# board2-0.net
KiCad netlist of a schematic drawn in EAGLE
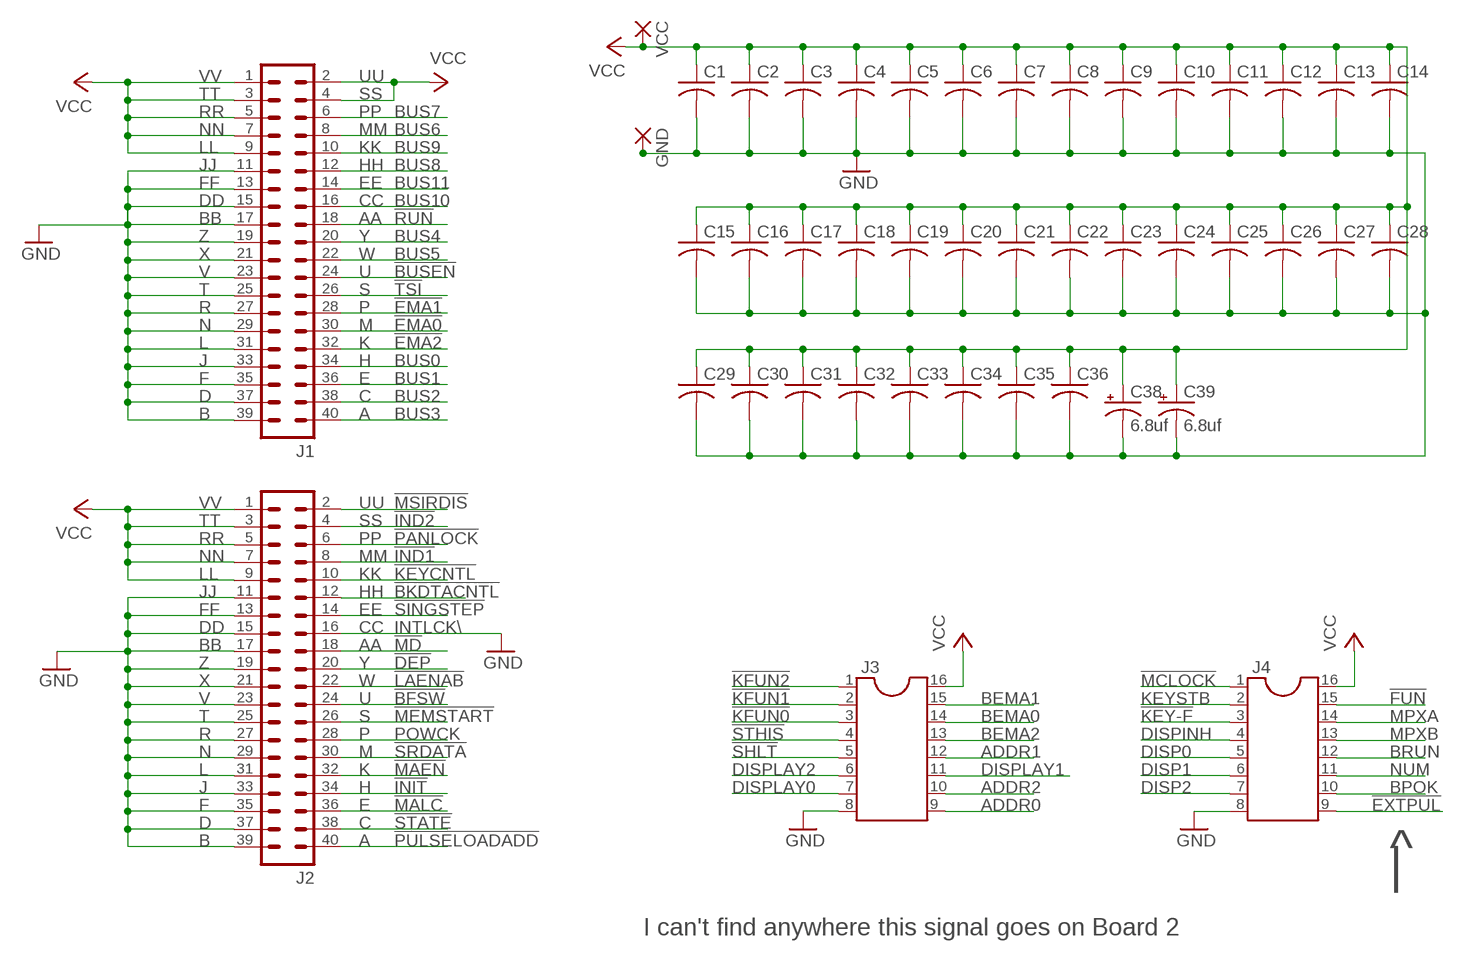
[diagram p0: schematic, sheet 1]
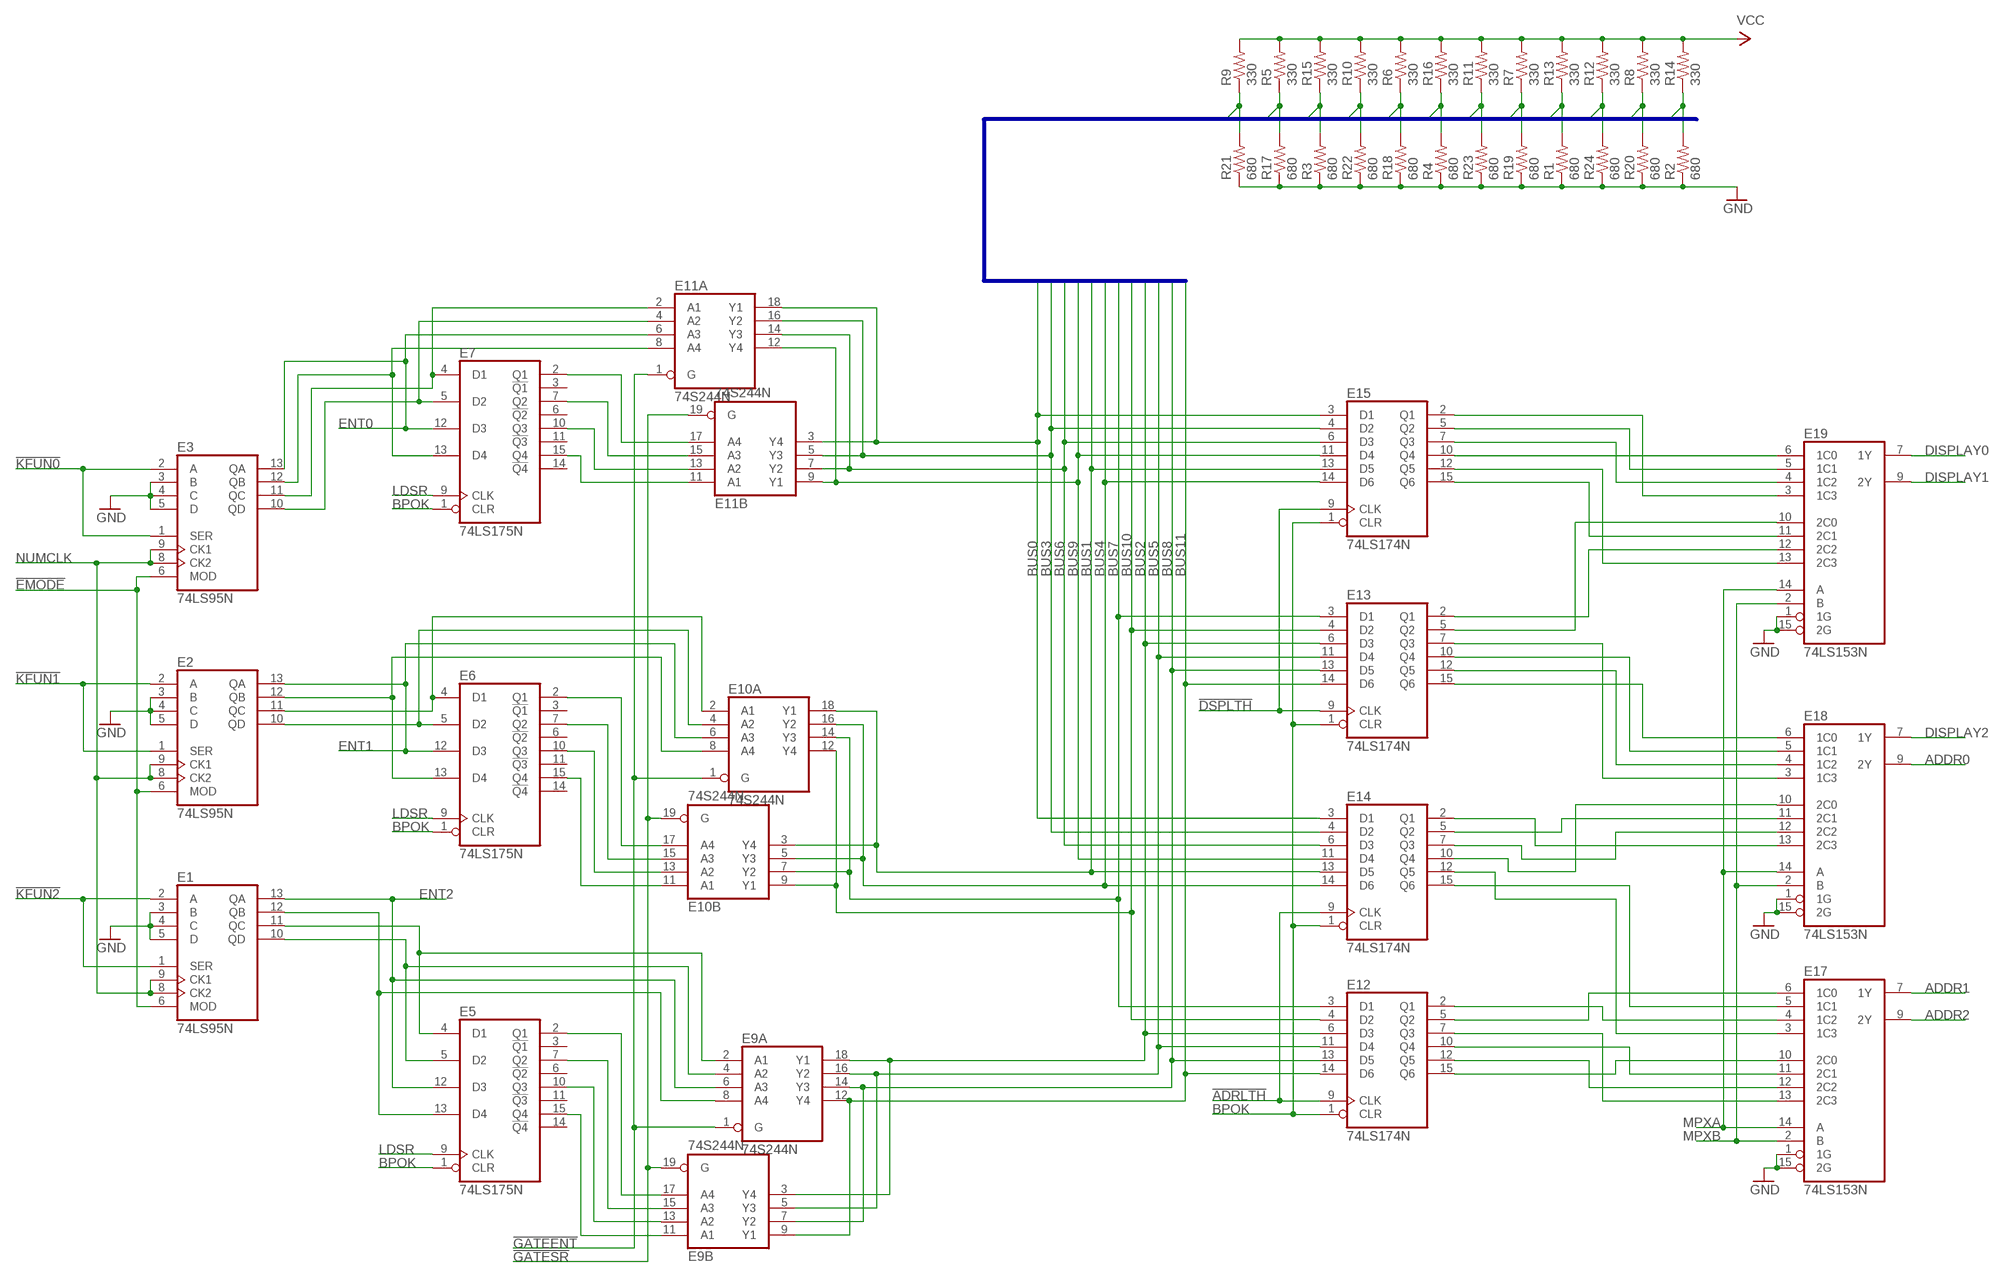
[diagram p1: schematic, sheet 2]
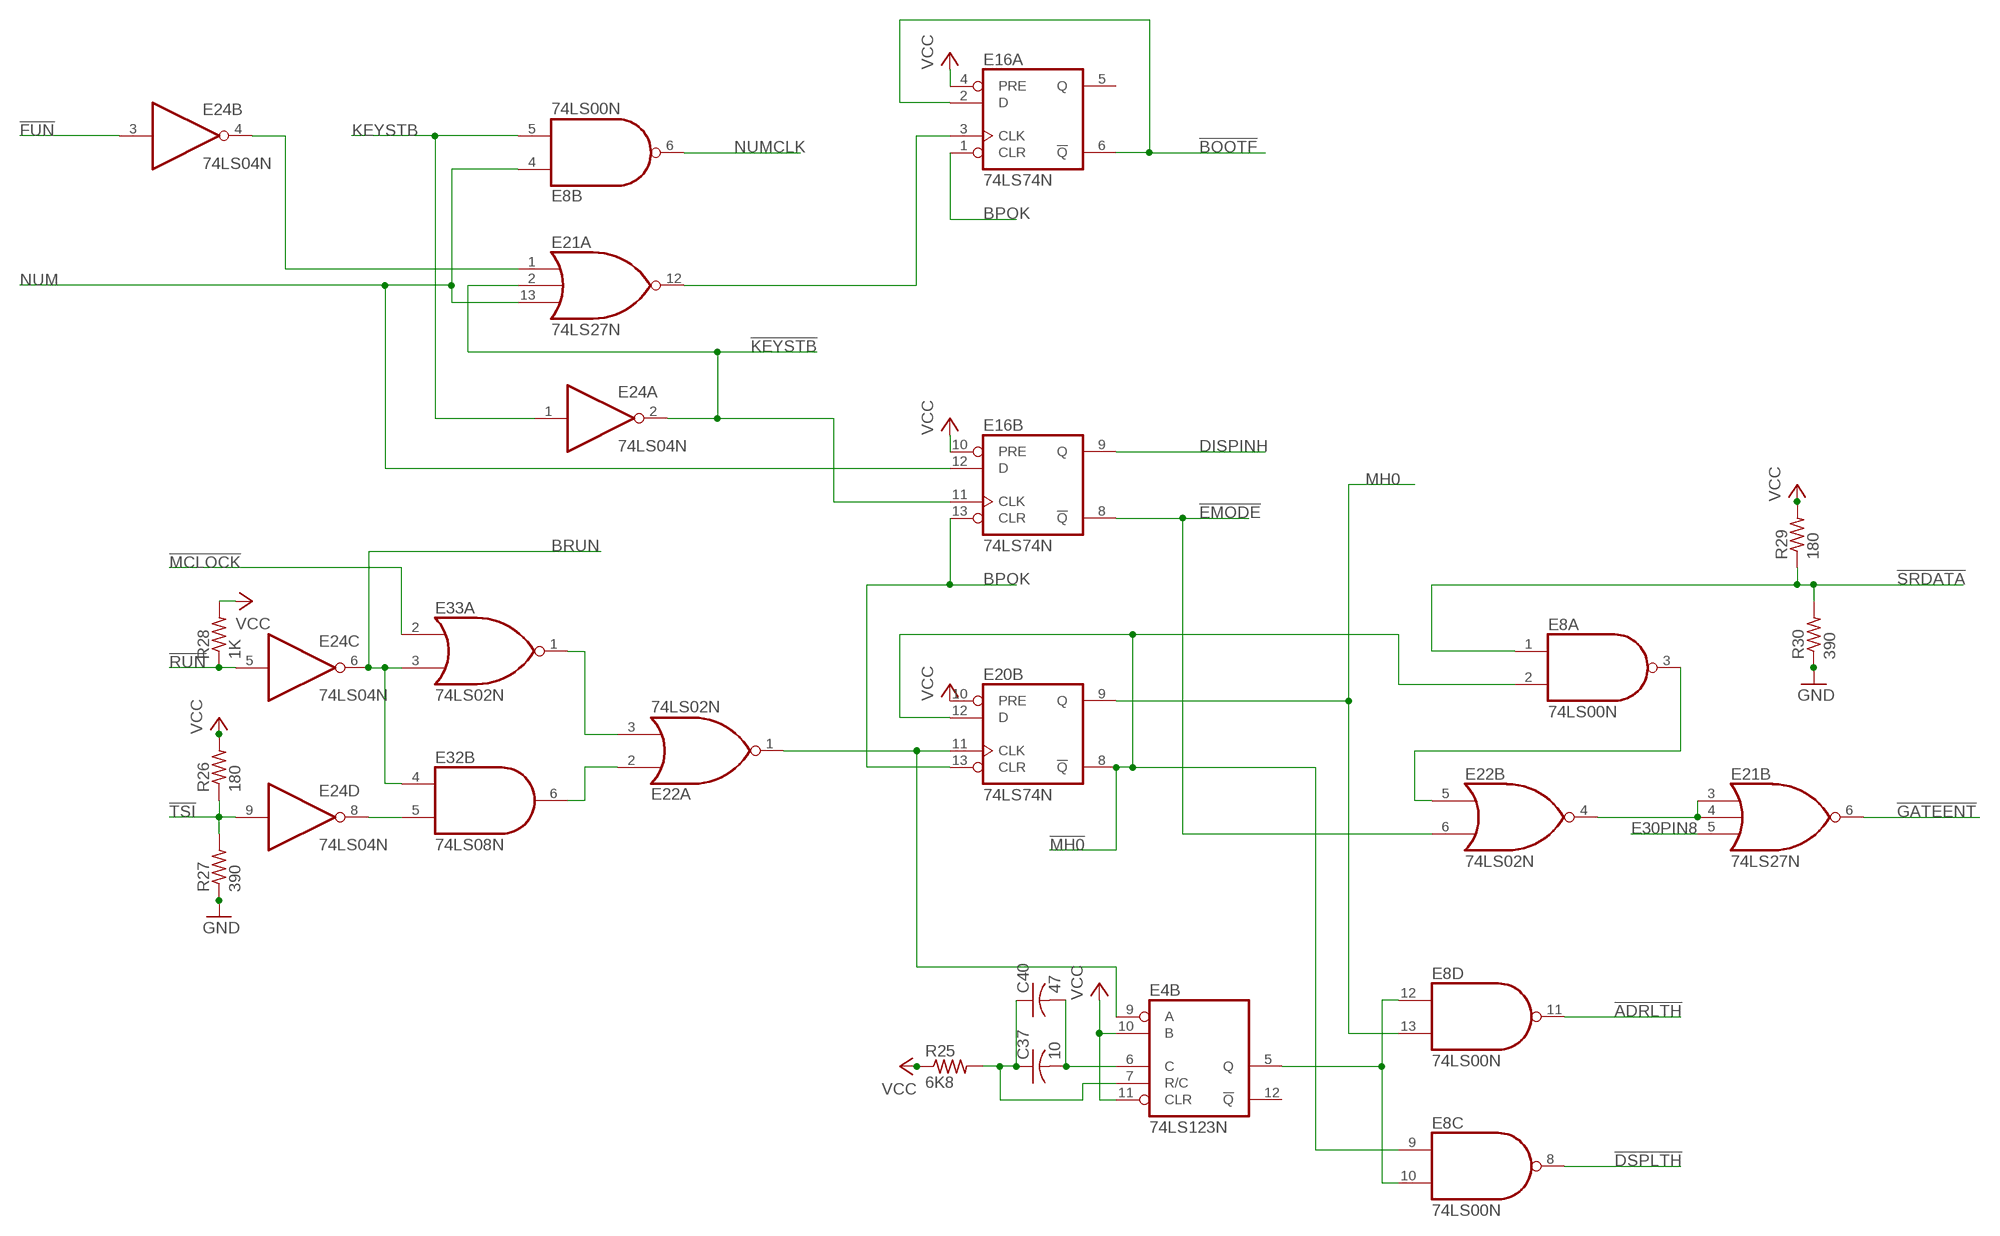
[diagram p2: schematic, sheet 3]
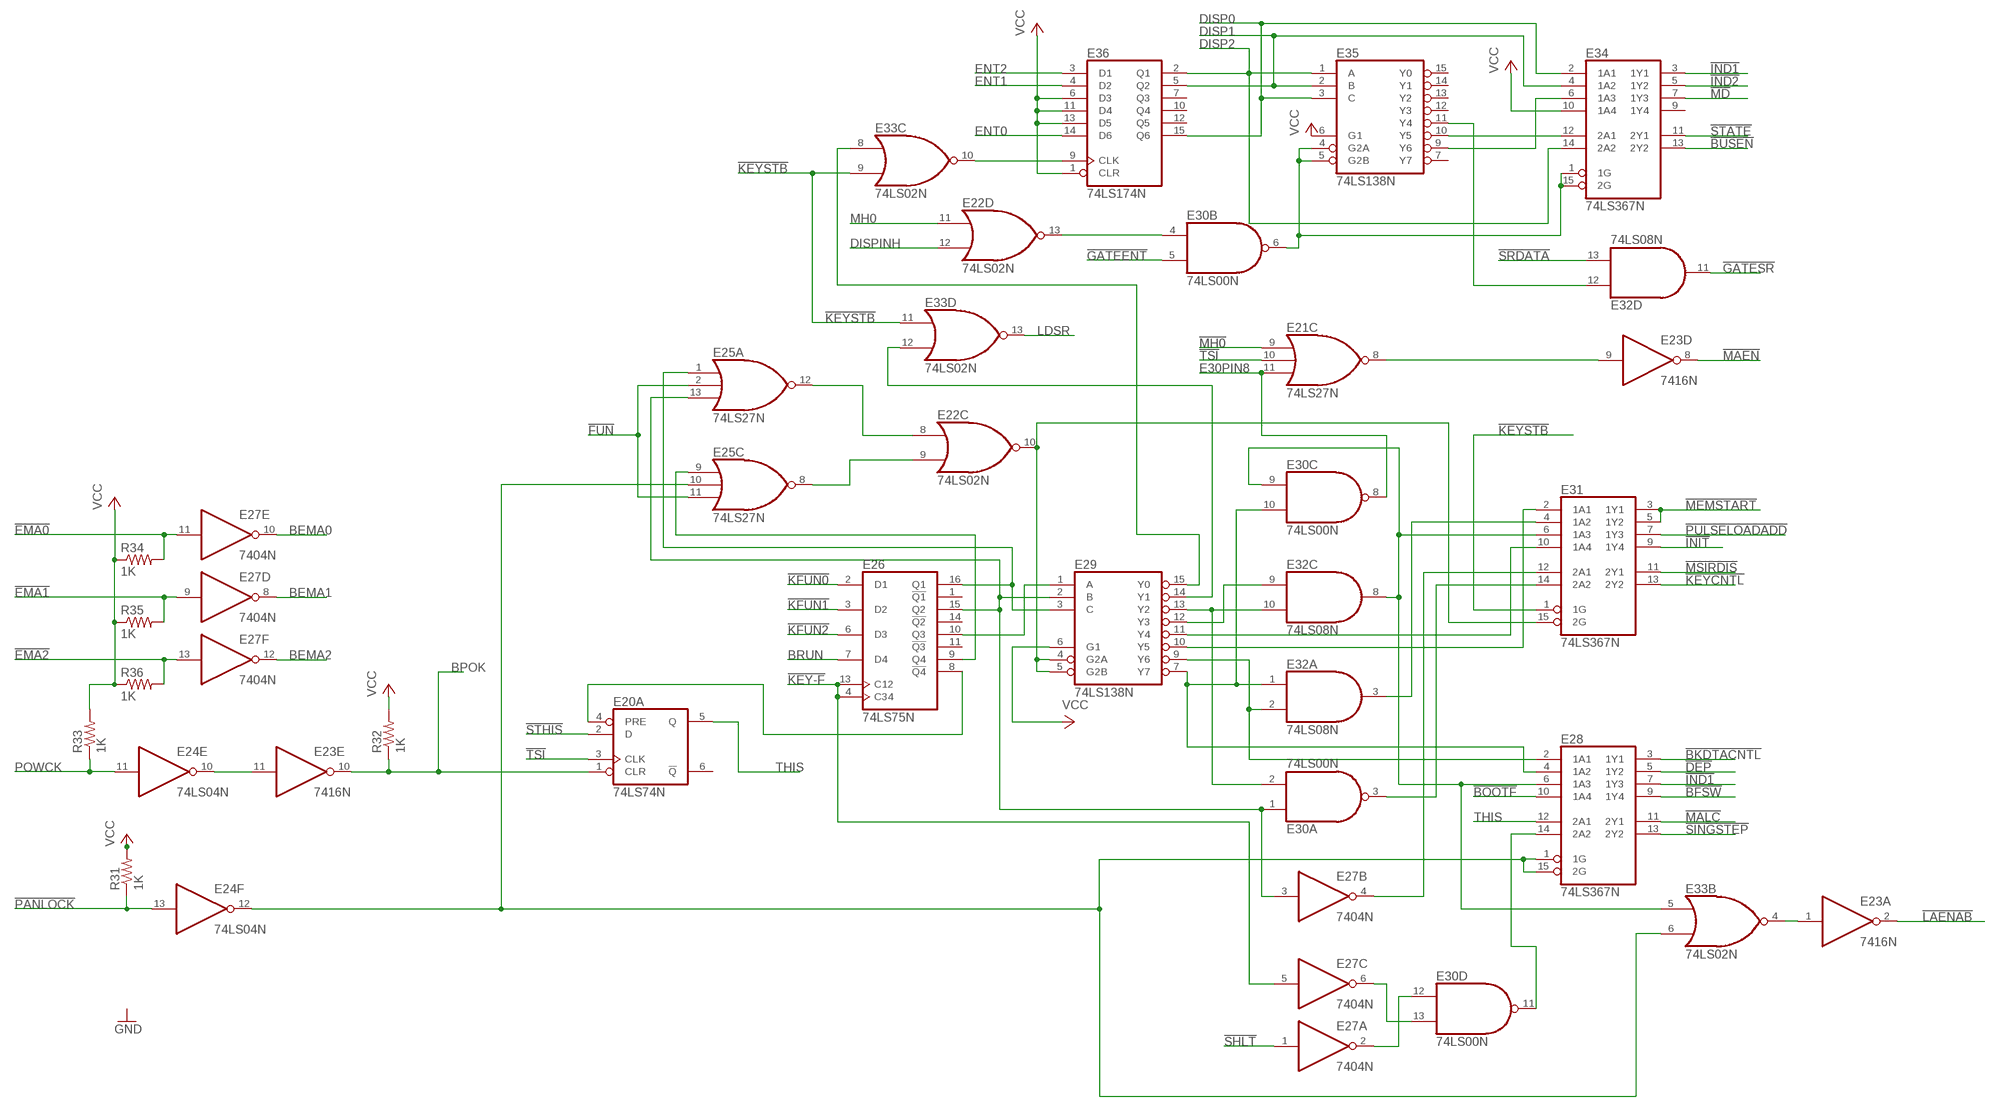
[diagram p3: schematic, sheet 4]

(export (version "E")
  (design (tool "Eeschema 10.0.6"))
  (components
    (comp (ref "C37")
      (value "10")
      (footprint "eagle-import:C050-025X075")
      (libsource (lib "eagle-import") (part "C-US050-025X075"))
    )
    (comp (ref "C40")
      (value "47")
      (footprint "eagle-import:C050-025X075")
      (libsource (lib "eagle-import") (part "C-US050-025X075"))
    )
    (comp (ref "E4")
      (value "74LS123N")
      (footprint "eagle-import:DIL16")
      (libsource (lib "eagle-import") (part "74123NLS"))
    )
    (comp (ref "E8")
      (value "74LS00N")
      (footprint "eagle-import:DIL14")
      (libsource (lib "eagle-import") (part "7400NLS"))
    )
    (comp (ref "E16")
      (value "74LS74N")
      (footprint "eagle-import:DIL14")
      (libsource (lib "eagle-import") (part "7474NLS"))
    )
    (comp (ref "E20")
      (value "74LS74N")
      (footprint "eagle-import:DIL14")
      (libsource (lib "eagle-import") (part "7474NLS"))
    )
    (comp (ref "E21")
      (value "74LS27N")
      (footprint "eagle-import:DIL14")
      (libsource (lib "eagle-import") (part "7427NLS"))
    )
    (comp (ref "E22")
      (value "74LS02N")
      (footprint "eagle-import:DIL14")
      (libsource (lib "eagle-import") (part "7402NLS"))
    )
    (comp (ref "E24")
      (value "74LS04N")
      (footprint "eagle-import:DIL14")
      (libsource (lib "eagle-import") (part "7404NLS"))
    )
    (comp (ref "E32")
      (value "74LS08N")
      (footprint "eagle-import:DIL14")
      (libsource (lib "eagle-import") (part "7408NLS"))
    )
    (comp (ref "E33")
      (value "74LS02N")
      (footprint "eagle-import:DIL14")
      (libsource (lib "eagle-import") (part "7402NLS"))
    )
    (comp (ref "R25")
      (value "6K8")
      (footprint "eagle-import:0207_10")
      (libsource (lib "eagle-import") (part "R-US_0207/10"))
    )
    (comp (ref "R26")
      (value "180")
      (footprint "eagle-import:0207_10")
      (libsource (lib "eagle-import") (part "R-US_0207/10"))
    )
    (comp (ref "R27")
      (value "390")
      (footprint "eagle-import:0207_10")
      (libsource (lib "eagle-import") (part "R-US_0207/10"))
    )
    (comp (ref "R28")
      (value "1K")
      (footprint "eagle-import:0207_10")
      (libsource (lib "eagle-import") (part "R-US_0207/10"))
    )
    (comp (ref "R29")
      (value "180")
      (footprint "eagle-import:0207_10")
      (libsource (lib "eagle-import") (part "R-US_0207/10"))
    )
    (comp (ref "R30")
      (value "390")
      (footprint "eagle-import:0207_10")
      (libsource (lib "eagle-import") (part "R-US_0207/10"))
    )
    (comp (ref "E1")
      (value "74LS95N")
      (footprint "eagle-import:DIL14")
      (libsource (lib "eagle-import") (part "7495NLS"))
    )
    (comp (ref "E2")
      (value "74LS95N")
      (footprint "eagle-import:DIL14")
      (libsource (lib "eagle-import") (part "7495NLS"))
    )
    (comp (ref "E3")
      (value "74LS95N")
      (footprint "eagle-import:DIL14")
      (libsource (lib "eagle-import") (part "7495NLS"))
    )
    (comp (ref "E5")
      (value "74LS175N")
      (footprint "eagle-import:DIL16")
      (libsource (lib "eagle-import") (part "74175NLS"))
    )
    (comp (ref "E6")
      (value "74LS175N")
      (footprint "eagle-import:DIL16")
      (libsource (lib "eagle-import") (part "74175NLS"))
    )
    (comp (ref "E7")
      (value "74LS175N")
      (footprint "eagle-import:DIL16")
      (libsource (lib "eagle-import") (part "74175NLS"))
    )
    (comp (ref "E9")
      (value "74S244N")
      (footprint "eagle-import:DIL20")
      (libsource (lib "eagle-import") (part "74244NS"))
    )
    (comp (ref "E10")
      (value "74S244N")
      (footprint "eagle-import:DIL20")
      (libsource (lib "eagle-import") (part "74244NS"))
    )
    (comp (ref "E11")
      (value "74S244N")
      (footprint "eagle-import:DIL20")
      (libsource (lib "eagle-import") (part "74244NS"))
    )
    (comp (ref "E12")
      (value "74LS174N")
      (footprint "eagle-import:DIL16")
      (libsource (lib "eagle-import") (part "74174NLS"))
    )
    (comp (ref "E13")
      (value "74LS174N")
      (footprint "eagle-import:DIL16")
      (libsource (lib "eagle-import") (part "74174NLS"))
    )
    (comp (ref "E14")
      (value "74LS174N")
      (footprint "eagle-import:DIL16")
      (libsource (lib "eagle-import") (part "74174NLS"))
    )
    (comp (ref "E15")
      (value "74LS174N")
      (footprint "eagle-import:DIL16")
      (libsource (lib "eagle-import") (part "74174NLS"))
    )
    (comp (ref "E17")
      (value "74LS153N")
      (footprint "eagle-import:DIL16")
      (libsource (lib "eagle-import") (part "74153NLS"))
    )
    (comp (ref "E18")
      (value "74LS153N")
      (footprint "eagle-import:DIL16")
      (libsource (lib "eagle-import") (part "74153NLS"))
    )
    (comp (ref "E19")
      (value "74LS153N")
      (footprint "eagle-import:DIL16")
      (libsource (lib "eagle-import") (part "74153NLS"))
    )
    (comp (ref "R1")
      (value "680")
      (footprint "eagle-import:0207_10")
      (libsource (lib "eagle-import") (part "R-US_0207/10"))
    )
    (comp (ref "R2")
      (value "680")
      (footprint "eagle-import:0207_10")
      (libsource (lib "eagle-import") (part "R-US_0207/10"))
    )
    (comp (ref "R3")
      (value "680")
      (footprint "eagle-import:0207_10")
      (libsource (lib "eagle-import") (part "R-US_0207/10"))
    )
    (comp (ref "R4")
      (value "680")
      (footprint "eagle-import:0207_10")
      (libsource (lib "eagle-import") (part "R-US_0207/10"))
    )
    (comp (ref "R5")
      (value "330")
      (footprint "eagle-import:0207_10")
      (libsource (lib "eagle-import") (part "R-US_0207/10"))
    )
    (comp (ref "R6")
      (value "330")
      (footprint "eagle-import:0207_10")
      (libsource (lib "eagle-import") (part "R-US_0207/10"))
    )
    (comp (ref "R7")
      (value "330")
      (footprint "eagle-import:0207_10")
      (libsource (lib "eagle-import") (part "R-US_0207/10"))
    )
    (comp (ref "R8")
      (value "330")
      (footprint "eagle-import:0207_10")
      (libsource (lib "eagle-import") (part "R-US_0207/10"))
    )
    (comp (ref "R9")
      (value "330")
      (footprint "eagle-import:0207_10")
      (libsource (lib "eagle-import") (part "R-US_0207/10"))
    )
    (comp (ref "R10")
      (value "330")
      (footprint "eagle-import:0207_10")
      (libsource (lib "eagle-import") (part "R-US_0207/10"))
    )
    (comp (ref "R11")
      (value "330")
      (footprint "eagle-import:0207_10")
      (libsource (lib "eagle-import") (part "R-US_0207/10"))
    )
    (comp (ref "R12")
      (value "330")
      (footprint "eagle-import:0207_10")
      (libsource (lib "eagle-import") (part "R-US_0207/10"))
    )
    (comp (ref "R13")
      (value "330")
      (footprint "eagle-import:0207_10")
      (libsource (lib "eagle-import") (part "R-US_0207/10"))
    )
    (comp (ref "R14")
      (value "330")
      (footprint "eagle-import:0207_10")
      (libsource (lib "eagle-import") (part "R-US_0207/10"))
    )
    (comp (ref "R15")
      (value "330")
      (footprint "eagle-import:0207_10")
      (libsource (lib "eagle-import") (part "R-US_0207/10"))
    )
    (comp (ref "R16")
      (value "330")
      (footprint "eagle-import:0207_10")
      (libsource (lib "eagle-import") (part "R-US_0207/10"))
    )
    (comp (ref "R17")
      (value "680")
      (footprint "eagle-import:0207_10")
      (libsource (lib "eagle-import") (part "R-US_0207/10"))
    )
    (comp (ref "R18")
      (value "680")
      (footprint "eagle-import:0207_10")
      (libsource (lib "eagle-import") (part "R-US_0207/10"))
    )
    (comp (ref "R19")
      (value "680")
      (footprint "eagle-import:0207_10")
      (libsource (lib "eagle-import") (part "R-US_0207/10"))
    )
    (comp (ref "R20")
      (value "680")
      (footprint "eagle-import:0207_10")
      (libsource (lib "eagle-import") (part "R-US_0207/10"))
    )
    (comp (ref "R21")
      (value "680")
      (footprint "eagle-import:0207_10")
      (libsource (lib "eagle-import") (part "R-US_0207/10"))
    )
    (comp (ref "R22")
      (value "680")
      (footprint "eagle-import:0207_10")
      (libsource (lib "eagle-import") (part "R-US_0207/10"))
    )
    (comp (ref "R23")
      (value "680")
      (footprint "eagle-import:0207_10")
      (libsource (lib "eagle-import") (part "R-US_0207/10"))
    )
    (comp (ref "R24")
      (value "680")
      (footprint "eagle-import:0207_10")
      (libsource (lib "eagle-import") (part "R-US_0207/10"))
    )
    (comp (ref "C1")
      (value "C-US050-025X075")
      (footprint "eagle-import:C050-025X075")
      (libsource (lib "eagle-import") (part "C-US050-025X075"))
    )
    (comp (ref "C2")
      (value "C-US050-025X075")
      (footprint "eagle-import:C050-025X075")
      (libsource (lib "eagle-import") (part "C-US050-025X075"))
    )
    (comp (ref "C3")
      (value "C-US050-025X075")
      (footprint "eagle-import:C050-025X075")
      (libsource (lib "eagle-import") (part "C-US050-025X075"))
    )
    (comp (ref "C4")
      (value "C-US050-025X075")
      (footprint "eagle-import:C050-025X075")
      (libsource (lib "eagle-import") (part "C-US050-025X075"))
    )
    (comp (ref "C5")
      (value "C-US050-025X075")
      (footprint "eagle-import:C050-025X075")
      (libsource (lib "eagle-import") (part "C-US050-025X075"))
    )
    (comp (ref "C6")
      (value "C-US050-025X075")
      (footprint "eagle-import:C050-025X075")
      (libsource (lib "eagle-import") (part "C-US050-025X075"))
    )
    (comp (ref "C7")
      (value "C-US050-025X075")
      (footprint "eagle-import:C050-025X075")
      (libsource (lib "eagle-import") (part "C-US050-025X075"))
    )
    (comp (ref "C8")
      (value "C-US050-025X075")
      (footprint "eagle-import:C050-025X075")
      (libsource (lib "eagle-import") (part "C-US050-025X075"))
    )
    (comp (ref "C9")
      (value "C-US050-025X075")
      (footprint "eagle-import:C050-025X075")
      (libsource (lib "eagle-import") (part "C-US050-025X075"))
    )
    (comp (ref "C10")
      (value "C-US050-025X075")
      (footprint "eagle-import:C050-025X075")
      (libsource (lib "eagle-import") (part "C-US050-025X075"))
    )
    (comp (ref "C11")
      (value "C-US050-025X075")
      (footprint "eagle-import:C050-025X075")
      (libsource (lib "eagle-import") (part "C-US050-025X075"))
    )
    (comp (ref "C12")
      (value "C-US050-025X075")
      (footprint "eagle-import:C050-025X075")
      (libsource (lib "eagle-import") (part "C-US050-025X075"))
    )
    (comp (ref "C13")
      (value "C-US050-025X075")
      (footprint "eagle-import:C050-025X075")
      (libsource (lib "eagle-import") (part "C-US050-025X075"))
    )
    (comp (ref "C14")
      (value "C-US050-025X075")
      (footprint "eagle-import:C050-025X075")
      (libsource (lib "eagle-import") (part "C-US050-025X075"))
    )
    (comp (ref "C15")
      (value "C-US050-025X075")
      (footprint "eagle-import:C050-025X075")
      (libsource (lib "eagle-import") (part "C-US050-025X075"))
    )
    (comp (ref "C16")
      (value "C-US050-025X075")
      (footprint "eagle-import:C050-025X075")
      (libsource (lib "eagle-import") (part "C-US050-025X075"))
    )
    (comp (ref "C17")
      (value "C-US050-025X075")
      (footprint "eagle-import:C050-025X075")
      (libsource (lib "eagle-import") (part "C-US050-025X075"))
    )
    (comp (ref "C18")
      (value "C-US050-025X075")
      (footprint "eagle-import:C050-025X075")
      (libsource (lib "eagle-import") (part "C-US050-025X075"))
    )
    (comp (ref "C19")
      (value "C-US050-025X075")
      (footprint "eagle-import:C050-025X075")
      (libsource (lib "eagle-import") (part "C-US050-025X075"))
    )
    (comp (ref "C20")
      (value "C-US050-025X075")
      (footprint "eagle-import:C050-025X075")
      (libsource (lib "eagle-import") (part "C-US050-025X075"))
    )
    (comp (ref "C21")
      (value "C-US050-025X075")
      (footprint "eagle-import:C050-025X075")
      (libsource (lib "eagle-import") (part "C-US050-025X075"))
    )
    (comp (ref "C22")
      (value "C-US050-025X075")
      (footprint "eagle-import:C050-025X075")
      (libsource (lib "eagle-import") (part "C-US050-025X075"))
    )
    (comp (ref "C23")
      (value "C-US050-025X075")
      (footprint "eagle-import:C050-025X075")
      (libsource (lib "eagle-import") (part "C-US050-025X075"))
    )
    (comp (ref "C24")
      (value "C-US050-025X075")
      (footprint "eagle-import:C050-025X075")
      (libsource (lib "eagle-import") (part "C-US050-025X075"))
    )
    (comp (ref "C25")
      (value "C-US050-025X075")
      (footprint "eagle-import:C050-025X075")
      (libsource (lib "eagle-import") (part "C-US050-025X075"))
    )
    (comp (ref "C26")
      (value "C-US050-025X075")
      (footprint "eagle-import:C050-025X075")
      (libsource (lib "eagle-import") (part "C-US050-025X075"))
    )
    (comp (ref "C27")
      (value "C-US050-025X075")
      (footprint "eagle-import:C050-025X075")
      (libsource (lib "eagle-import") (part "C-US050-025X075"))
    )
    (comp (ref "C28")
      (value "C-US050-025X075")
      (footprint "eagle-import:C050-025X075")
      (libsource (lib "eagle-import") (part "C-US050-025X075"))
    )
    (comp (ref "C29")
      (value "C-US050-025X075")
      (footprint "eagle-import:C050-025X075")
      (libsource (lib "eagle-import") (part "C-US050-025X075"))
    )
    (comp (ref "C30")
      (value "C-US050-025X075")
      (footprint "eagle-import:C050-025X075")
      (libsource (lib "eagle-import") (part "C-US050-025X075"))
    )
    (comp (ref "C31")
      (value "C-US050-025X075")
      (footprint "eagle-import:C050-025X075")
      (libsource (lib "eagle-import") (part "C-US050-025X075"))
    )
    (comp (ref "C32")
      (value "C-US050-025X075")
      (footprint "eagle-import:C050-025X075")
      (libsource (lib "eagle-import") (part "C-US050-025X075"))
    )
    (comp (ref "C33")
      (value "C-US050-025X075")
      (footprint "eagle-import:C050-025X075")
      (libsource (lib "eagle-import") (part "C-US050-025X075"))
    )
    (comp (ref "C34")
      (value "C-US050-025X075")
      (footprint "eagle-import:C050-025X075")
      (libsource (lib "eagle-import") (part "C-US050-025X075"))
    )
    (comp (ref "C35")
      (value "C-US050-025X075")
      (footprint "eagle-import:C050-025X075")
      (libsource (lib "eagle-import") (part "C-US050-025X075"))
    )
    (comp (ref "C36")
      (value "C-US050-025X075")
      (footprint "eagle-import:C050-025X075")
      (libsource (lib "eagle-import") (part "C-US050-025X075"))
    )
    (comp (ref "C38")
      (value "6.8uf")
      (footprint "eagle-import:E15-5")
      (libsource (lib "eagle-import") (part "CPOL-USE15-5AXIAL"))
    )
    (comp (ref "C39")
      (value "6.8uf")
      (footprint "eagle-import:E15-5")
      (libsource (lib "eagle-import") (part "CPOL-USE15-5AXIAL"))
    )
    (comp (ref "GND")
      (value "3,81/1,4")
      (footprint "eagle-import:3,81_1,4")
      (libsource (lib "eagle-import") (part "3,81/1,4"))
    )
    (comp (ref "J1")
      (value "40H")
      (footprint "eagle-import:40H")
      (libsource (lib "eagle-import") (part "40H"))
    )
    (comp (ref "J2")
      (value "40H")
      (footprint "eagle-import:40H")
      (libsource (lib "eagle-import") (part "40H"))
    )
    (comp (ref "J3")
      (value "DIL16S")
      (footprint "eagle-import:SOCKET-16")
      (libsource (lib "eagle-import") (part "DIL16S"))
    )
    (comp (ref "J4")
      (value "DIL16S")
      (footprint "eagle-import:SOCKET-16")
      (libsource (lib "eagle-import") (part "DIL16S"))
    )
    (comp (ref "VCC")
      (value "3,81/1,4")
      (footprint "eagle-import:3,81_1,4")
      (libsource (lib "eagle-import") (part "3,81/1,4"))
    )
    (comp (ref "E23")
      (value "7416N")
      (footprint "eagle-import:DIL14")
      (libsource (lib "eagle-import") (part "7416N"))
    )
    (comp (ref "E25")
      (value "74LS27N")
      (footprint "eagle-import:DIL14")
      (libsource (lib "eagle-import") (part "7427NLS"))
    )
    (comp (ref "E26")
      (value "74LS75N")
      (footprint "eagle-import:DIL16")
      (libsource (lib "eagle-import") (part "7475NLS"))
    )
    (comp (ref "E27")
      (value "7404N")
      (footprint "eagle-import:DIL14")
      (libsource (lib "eagle-import") (part "7404N"))
    )
    (comp (ref "E28")
      (value "74LS367N")
      (footprint "eagle-import:DIL16")
      (libsource (lib "eagle-import") (part "74367N"))
    )
    (comp (ref "E29")
      (value "74LS138N")
      (footprint "eagle-import:DIL16")
      (libsource (lib "eagle-import") (part "74138NLS"))
    )
    (comp (ref "E30")
      (value "74LS00N")
      (footprint "eagle-import:DIL14")
      (libsource (lib "eagle-import") (part "7400NLS"))
    )
    (comp (ref "E31")
      (value "74LS367N")
      (footprint "eagle-import:DIL16")
      (libsource (lib "eagle-import") (part "74367N"))
    )
    (comp (ref "E34")
      (value "74LS367N")
      (footprint "eagle-import:DIL16")
      (libsource (lib "eagle-import") (part "74367N"))
    )
    (comp (ref "E35")
      (value "74LS138N")
      (footprint "eagle-import:DIL16")
      (libsource (lib "eagle-import") (part "74138NLS"))
    )
    (comp (ref "E36")
      (value "74LS174N")
      (footprint "eagle-import:DIL16")
      (libsource (lib "eagle-import") (part "74174NLS"))
    )
    (comp (ref "R31")
      (value "1K")
      (footprint "eagle-import:0207_10")
      (libsource (lib "eagle-import") (part "R-US_0207/10"))
    )
    (comp (ref "R32")
      (value "1K")
      (footprint "eagle-import:0207_10")
      (libsource (lib "eagle-import") (part "R-US_0207/10"))
    )
    (comp (ref "R33")
      (value "1K")
      (footprint "eagle-import:0207_10")
      (libsource (lib "eagle-import") (part "R-US_0207/10"))
    )
    (comp (ref "R34")
      (value "1K")
      (footprint "eagle-import:0207_10")
      (libsource (lib "eagle-import") (part "R-US_0207/10"))
    )
    (comp (ref "R35")
      (value "1K")
      (footprint "eagle-import:0207_10")
      (libsource (lib "eagle-import") (part "R-US_0207/10"))
    )
    (comp (ref "R36")
      (value "1K")
      (footprint "eagle-import:0207_10")
      (libsource (lib "eagle-import") (part "R-US_0207/10"))
    )
  )
  (nets
    (net (code "1") (name "ADDR0") (class "Default")
      (node (ref "E18") (pin "9") (pinfunction "2Y_9") (pintype "output"))
      (node (ref "J3") (pin "9") (pinfunction "9_9") (pintype "passive"))
    )
    (net (code "2") (name "ADDR1") (class "Default")
      (node (ref "E17") (pin "7") (pinfunction "1Y_7") (pintype "output"))
      (node (ref "J3") (pin "12") (pinfunction "12_12") (pintype "passive"))
    )
    (net (code "3") (name "ADDR2") (class "Default")
      (node (ref "E17") (pin "9") (pinfunction "2Y_9") (pintype "output"))
      (node (ref "J3") (pin "10") (pinfunction "10_10") (pintype "passive"))
    )
    (net (code "4") (name "BEMA0") (class "Default")
      (node (ref "E27") (pin "10") (pinfunction "O_10") (pintype "output"))
      (node (ref "J3") (pin "14") (pinfunction "14_14") (pintype "passive"))
    )
    (net (code "5") (name "BEMA1") (class "Default")
      (node (ref "E27") (pin "8") (pinfunction "O_8") (pintype "output"))
      (node (ref "J3") (pin "15") (pinfunction "15_15") (pintype "passive"))
    )
    (net (code "6") (name "BEMA2") (class "Default")
      (node (ref "E27") (pin "12") (pinfunction "O_12") (pintype "output"))
      (node (ref "J3") (pin "13") (pinfunction "13_13") (pintype "passive"))
    )
    (net (code "7") (name "BPOK") (class "Default")
      (node (ref "E12") (pin "1") (pinfunction "CLR_1") (pintype "input"))
      (node (ref "E13") (pin "1") (pinfunction "CLR_1") (pintype "input"))
      (node (ref "E14") (pin "1") (pinfunction "CLR_1") (pintype "input"))
      (node (ref "E15") (pin "1") (pinfunction "CLR_1") (pintype "input"))
      (node (ref "E16") (pin "1") (pinfunction "CLR_1") (pintype "input"))
      (node (ref "E16") (pin "13") (pinfunction "CLR_13") (pintype "input"))
      (node (ref "E20") (pin "1") (pinfunction "CLR_1") (pintype "input"))
      (node (ref "E20") (pin "13") (pinfunction "CLR_13") (pintype "input"))
      (node (ref "E23") (pin "10") (pinfunction "O_10") (pintype "open_collector"))
      (node (ref "E5") (pin "1") (pinfunction "CLR_1") (pintype "input"))
      (node (ref "E6") (pin "1") (pinfunction "CLR_1") (pintype "input"))
      (node (ref "E7") (pin "1") (pinfunction "CLR_1") (pintype "input"))
      (node (ref "J4") (pin "10") (pinfunction "10_10") (pintype "passive"))
      (node (ref "R32") (pin "1") (pinfunction "1_1") (pintype "passive"))
    )
    (net (code "8") (name "BRUN") (class "Default")
      (node (ref "E24") (pin "6") (pinfunction "O_6") (pintype "output"))
      (node (ref "E26") (pin "7") (pinfunction "D4_7") (pintype "input"))
      (node (ref "E32") (pin "4") (pinfunction "I0_4") (pintype "input"))
      (node (ref "E33") (pin "3") (pinfunction "I1_3") (pintype "input"))
      (node (ref "J4") (pin "12") (pinfunction "12_12") (pintype "passive"))
    )
    (net (code "9") (name "BUS0") (class "Default")
      (node (ref "E11") (pin "18") (pinfunction "Y1_18") (pintype "tri_state"))
      (node (ref "E11") (pin "3") (pinfunction "Y4_3") (pintype "tri_state"))
      (node (ref "E14") (pin "3") (pinfunction "D1_3") (pintype "input"))
      (node (ref "E15") (pin "3") (pinfunction "D1_3") (pintype "input"))
      (node (ref "J1") (pin "34") (pinfunction "34_34") (pintype "passive"))
      (node (ref "R21") (pin "2") (pinfunction "2_2") (pintype "passive"))
      (node (ref "R9") (pin "1") (pinfunction "1_1") (pintype "passive"))
    )
    (net (code "10") (name "BUS1") (class "Default")
      (node (ref "E10") (pin "18") (pinfunction "Y1_18") (pintype "tri_state"))
      (node (ref "E10") (pin "3") (pinfunction "Y4_3") (pintype "tri_state"))
      (node (ref "E14") (pin "13") (pinfunction "D5_13") (pintype "input"))
      (node (ref "E15") (pin "13") (pinfunction "D5_13") (pintype "input"))
      (node (ref "J1") (pin "36") (pinfunction "36_36") (pintype "passive"))
      (node (ref "R17") (pin "2") (pinfunction "2_2") (pintype "passive"))
      (node (ref "R5") (pin "1") (pinfunction "1_1") (pintype "passive"))
    )
    (net (code "11") (name "BUS2") (class "Default")
      (node (ref "E12") (pin "6") (pinfunction "D3_6") (pintype "input"))
      (node (ref "E13") (pin "6") (pinfunction "D3_6") (pintype "input"))
      (node (ref "E9") (pin "18") (pinfunction "Y1_18") (pintype "tri_state"))
      (node (ref "E9") (pin "3") (pinfunction "Y4_3") (pintype "tri_state"))
      (node (ref "J1") (pin "38") (pinfunction "38_38") (pintype "passive"))
      (node (ref "R15") (pin "1") (pinfunction "1_1") (pintype "passive"))
      (node (ref "R3") (pin "2") (pinfunction "2_2") (pintype "passive"))
    )
    (net (code "12") (name "BUS3") (class "Default")
      (node (ref "E11") (pin "16") (pinfunction "Y2_16") (pintype "tri_state"))
      (node (ref "E11") (pin "5") (pinfunction "Y3_5") (pintype "tri_state"))
      (node (ref "E14") (pin "4") (pinfunction "D2_4") (pintype "input"))
      (node (ref "E15") (pin "4") (pinfunction "D2_4") (pintype "input"))
      (node (ref "J1") (pin "40") (pinfunction "40_40") (pintype "passive"))
      (node (ref "R10") (pin "1") (pinfunction "1_1") (pintype "passive"))
      (node (ref "R22") (pin "2") (pinfunction "2_2") (pintype "passive"))
    )
    (net (code "13") (name "BUS4") (class "Default")
      (node (ref "E10") (pin "16") (pinfunction "Y2_16") (pintype "tri_state"))
      (node (ref "E10") (pin "5") (pinfunction "Y3_5") (pintype "tri_state"))
      (node (ref "E14") (pin "14") (pinfunction "D6_14") (pintype "input"))
      (node (ref "E15") (pin "14") (pinfunction "D6_14") (pintype "input"))
      (node (ref "J1") (pin "20") (pinfunction "20_20") (pintype "passive"))
      (node (ref "R18") (pin "2") (pinfunction "2_2") (pintype "passive"))
      (node (ref "R6") (pin "1") (pinfunction "1_1") (pintype "passive"))
    )
    (net (code "14") (name "BUS5") (class "Default")
      (node (ref "E12") (pin "11") (pinfunction "D4_11") (pintype "input"))
      (node (ref "E13") (pin "11") (pinfunction "D4_11") (pintype "input"))
      (node (ref "E9") (pin "16") (pinfunction "Y2_16") (pintype "tri_state"))
      (node (ref "E9") (pin "5") (pinfunction "Y3_5") (pintype "tri_state"))
      (node (ref "J1") (pin "22") (pinfunction "22_22") (pintype "passive"))
      (node (ref "R16") (pin "1") (pinfunction "1_1") (pintype "passive"))
      (node (ref "R4") (pin "2") (pinfunction "2_2") (pintype "passive"))
    )
    (net (code "15") (name "BUS6") (class "Default")
      (node (ref "E11") (pin "14") (pinfunction "Y3_14") (pintype "tri_state"))
      (node (ref "E11") (pin "7") (pinfunction "Y2_7") (pintype "tri_state"))
      (node (ref "E14") (pin "6") (pinfunction "D3_6") (pintype "input"))
      (node (ref "E15") (pin "6") (pinfunction "D3_6") (pintype "input"))
      (node (ref "J1") (pin "8") (pinfunction "8_8") (pintype "passive"))
      (node (ref "R11") (pin "1") (pinfunction "1_1") (pintype "passive"))
      (node (ref "R23") (pin "2") (pinfunction "2_2") (pintype "passive"))
    )
    (net (code "16") (name "BUS7") (class "Default")
      (node (ref "E10") (pin "14") (pinfunction "Y3_14") (pintype "tri_state"))
      (node (ref "E10") (pin "7") (pinfunction "Y2_7") (pintype "tri_state"))
      (node (ref "E12") (pin "3") (pinfunction "D1_3") (pintype "input"))
      (node (ref "E13") (pin "3") (pinfunction "D1_3") (pintype "input"))
      (node (ref "J1") (pin "6") (pinfunction "6_6") (pintype "passive"))
      (node (ref "R19") (pin "2") (pinfunction "2_2") (pintype "passive"))
      (node (ref "R7") (pin "1") (pinfunction "1_1") (pintype "passive"))
    )
    (net (code "17") (name "BUS8") (class "Default")
      (node (ref "E12") (pin "13") (pinfunction "D5_13") (pintype "input"))
      (node (ref "E13") (pin "13") (pinfunction "D5_13") (pintype "input"))
      (node (ref "E9") (pin "14") (pinfunction "Y3_14") (pintype "tri_state"))
      (node (ref "E9") (pin "7") (pinfunction "Y2_7") (pintype "tri_state"))
      (node (ref "J1") (pin "12") (pinfunction "12_12") (pintype "passive"))
      (node (ref "R1") (pin "2") (pinfunction "2_2") (pintype "passive"))
      (node (ref "R12") (pin "1") (pinfunction "1_1") (pintype "passive"))
      (node (ref "R13") (pin "1") (pinfunction "1_1") (pintype "passive"))
      (node (ref "R24") (pin "2") (pinfunction "2_2") (pintype "passive"))
    )
    (net (code "18") (name "BUS9") (class "Default")
      (node (ref "E11") (pin "12") (pinfunction "Y4_12") (pintype "tri_state"))
      (node (ref "E11") (pin "9") (pinfunction "Y1_9") (pintype "tri_state"))
      (node (ref "E14") (pin "11") (pinfunction "D4_11") (pintype "input"))
      (node (ref "E15") (pin "11") (pinfunction "D4_11") (pintype "input"))
      (node (ref "J1") (pin "10") (pinfunction "10_10") (pintype "passive"))
    )
    (net (code "19") (name "BUS10") (class "Default")
      (node (ref "E10") (pin "12") (pinfunction "Y4_12") (pintype "tri_state"))
      (node (ref "E10") (pin "9") (pinfunction "Y1_9") (pintype "tri_state"))
      (node (ref "E12") (pin "4") (pinfunction "D2_4") (pintype "input"))
      (node (ref "E13") (pin "4") (pinfunction "D2_4") (pintype "input"))
      (node (ref "J1") (pin "16") (pinfunction "16_16") (pintype "passive"))
      (node (ref "R20") (pin "2") (pinfunction "2_2") (pintype "passive"))
      (node (ref "R8") (pin "1") (pinfunction "1_1") (pintype "passive"))
    )
    (net (code "20") (name "BUS11") (class "Default")
      (node (ref "E12") (pin "14") (pinfunction "D6_14") (pintype "input"))
      (node (ref "E13") (pin "14") (pinfunction "D6_14") (pintype "input"))
      (node (ref "E9") (pin "12") (pinfunction "Y4_12") (pintype "tri_state"))
      (node (ref "E9") (pin "9") (pinfunction "Y1_9") (pintype "tri_state"))
      (node (ref "J1") (pin "14") (pinfunction "14_14") (pintype "passive"))
      (node (ref "R14") (pin "1") (pinfunction "1_1") (pintype "passive"))
      (node (ref "R2") (pin "2") (pinfunction "2_2") (pintype "passive"))
    )
    (net (code "21") (name "DISP0") (class "Default")
      (node (ref "E34") (pin "2") (pinfunction "1A1_2") (pintype "input"))
      (node (ref "E35") (pin "3") (pinfunction "C_3") (pintype "input"))
      (node (ref "E36") (pin "15") (pinfunction "Q6_15") (pintype "output"))
      (node (ref "J4") (pin "5") (pinfunction "5_5") (pintype "passive"))
    )
    (net (code "22") (name "DISP1") (class "Default")
      (node (ref "E34") (pin "4") (pinfunction "1A2_4") (pintype "input"))
      (node (ref "E35") (pin "2") (pinfunction "B_2") (pintype "input"))
      (node (ref "E36") (pin "5") (pinfunction "Q2_5") (pintype "output"))
      (node (ref "J4") (pin "6") (pinfunction "6_6") (pintype "passive"))
    )
    (net (code "23") (name "DISP2") (class "Default")
      (node (ref "E34") (pin "14") (pinfunction "2A2_14") (pintype "input"))
      (node (ref "E35") (pin "1") (pinfunction "A_1") (pintype "input"))
      (node (ref "E36") (pin "2") (pinfunction "Q1_2") (pintype "output"))
      (node (ref "J4") (pin "7") (pinfunction "7_7") (pintype "passive"))
    )
    (net (code "24") (name "DISPINH") (class "Default")
      (node (ref "E16") (pin "9") (pinfunction "Q_9") (pintype "output"))
      (node (ref "E22") (pin "12") (pinfunction "I1_12") (pintype "input"))
      (node (ref "J4") (pin "4") (pinfunction "4_4") (pintype "passive"))
    )
    (net (code "25") (name "DISPLAY0") (class "Default")
      (node (ref "E19") (pin "7") (pinfunction "1Y_7") (pintype "output"))
      (node (ref "J3") (pin "7") (pinfunction "7_7") (pintype "passive"))
    )
    (net (code "26") (name "DISPLAY1") (class "Default")
      (node (ref "E19") (pin "9") (pinfunction "2Y_9") (pintype "output"))
      (node (ref "J3") (pin "11") (pinfunction "11_11") (pintype "passive"))
    )
    (net (code "27") (name "DISPLAY2") (class "Default")
      (node (ref "E18") (pin "7") (pinfunction "1Y_7") (pintype "output"))
      (node (ref "J3") (pin "6") (pinfunction "6_6") (pintype "passive"))
    )
    (net (code "28") (name "E30PIN8") (class "Default")
      (node (ref "E21") (pin "11") (pinfunction "I2_11") (pintype "input"))
      (node (ref "E21") (pin "5") (pinfunction "I2_5") (pintype "input"))
      (node (ref "E30") (pin "8") (pinfunction "O_8") (pintype "output"))
    )
    (net (code "29") (name "ENT0") (class "Default")
      (node (ref "E11") (pin "6") (pinfunction "A3_6") (pintype "input"))
      (node (ref "E3") (pin "13") (pinfunction "QA_13") (pintype "output"))
      (node (ref "E36") (pin "14") (pinfunction "D6_14") (pintype "input"))
      (node (ref "E7") (pin "12") (pinfunction "D3_12") (pintype "input"))
    )
    (net (code "30") (name "ENT1") (class "Default")
      (node (ref "E10") (pin "6") (pinfunction "A3_6") (pintype "input"))
      (node (ref "E2") (pin "13") (pinfunction "QA_13") (pintype "output"))
      (node (ref "E36") (pin "4") (pinfunction "D2_4") (pintype "input"))
      (node (ref "E6") (pin "12") (pinfunction "D3_12") (pintype "input"))
    )
    (net (code "31") (name "ENT2") (class "Default")
      (node (ref "E1") (pin "13") (pinfunction "QA_13") (pintype "output"))
      (node (ref "E36") (pin "3") (pinfunction "D1_3") (pintype "input"))
      (node (ref "E5") (pin "12") (pinfunction "D3_12") (pintype "input"))
      (node (ref "E9") (pin "6") (pinfunction "A3_6") (pintype "input"))
    )
    (net (code "32") (name "GND") (class "Default")
      (node (ref "C1") (pin "2") (pinfunction "2_2") (pintype "passive"))
      (node (ref "C10") (pin "2") (pinfunction "2_2") (pintype "passive"))
      (node (ref "C11") (pin "2") (pinfunction "2_2") (pintype "passive"))
      (node (ref "C12") (pin "2") (pinfunction "2_2") (pintype "passive"))
      (node (ref "C13") (pin "2") (pinfunction "2_2") (pintype "passive"))
      (node (ref "C14") (pin "2") (pinfunction "2_2") (pintype "passive"))
      (node (ref "C15") (pin "2") (pinfunction "2_2") (pintype "passive"))
      (node (ref "C16") (pin "2") (pinfunction "2_2") (pintype "passive"))
      (node (ref "C17") (pin "2") (pinfunction "2_2") (pintype "passive"))
      (node (ref "C18") (pin "2") (pinfunction "2_2") (pintype "passive"))
      (node (ref "C19") (pin "2") (pinfunction "2_2") (pintype "passive"))
      (node (ref "C2") (pin "2") (pinfunction "2_2") (pintype "passive"))
      (node (ref "C20") (pin "2") (pinfunction "2_2") (pintype "passive"))
      (node (ref "C21") (pin "2") (pinfunction "2_2") (pintype "passive"))
      (node (ref "C22") (pin "2") (pinfunction "2_2") (pintype "passive"))
      (node (ref "C23") (pin "2") (pinfunction "2_2") (pintype "passive"))
      (node (ref "C24") (pin "2") (pinfunction "2_2") (pintype "passive"))
      (node (ref "C25") (pin "2") (pinfunction "2_2") (pintype "passive"))
      (node (ref "C26") (pin "2") (pinfunction "2_2") (pintype "passive"))
      (node (ref "C27") (pin "2") (pinfunction "2_2") (pintype "passive"))
      (node (ref "C28") (pin "2") (pinfunction "2_2") (pintype "passive"))
      (node (ref "C29") (pin "2") (pinfunction "2_2") (pintype "passive"))
      (node (ref "C3") (pin "2") (pinfunction "2_2") (pintype "passive"))
      (node (ref "C30") (pin "2") (pinfunction "2_2") (pintype "passive"))
      (node (ref "C31") (pin "2") (pinfunction "2_2") (pintype "passive"))
      (node (ref "C32") (pin "2") (pinfunction "2_2") (pintype "passive"))
      (node (ref "C33") (pin "2") (pinfunction "2_2") (pintype "passive"))
      (node (ref "C34") (pin "2") (pinfunction "2_2") (pintype "passive"))
      (node (ref "C35") (pin "2") (pinfunction "2_2") (pintype "passive"))
      (node (ref "C36") (pin "2") (pinfunction "2_2") (pintype "passive"))
      (node (ref "C38") (pin "-") (pinfunction "-_-") (pintype "passive"))
      (node (ref "C39") (pin "-") (pinfunction "-_-") (pintype "passive"))
      (node (ref "C4") (pin "2") (pinfunction "2_2") (pintype "passive"))
      (node (ref "C5") (pin "2") (pinfunction "2_2") (pintype "passive"))
      (node (ref "C6") (pin "2") (pinfunction "2_2") (pintype "passive"))
      (node (ref "C7") (pin "2") (pinfunction "2_2") (pintype "passive"))
      (node (ref "C8") (pin "2") (pinfunction "2_2") (pintype "passive"))
      (node (ref "C9") (pin "2") (pinfunction "2_2") (pintype "passive"))
      (node (ref "E1") (pin "3") (pinfunction "B_3") (pintype "input"))
      (node (ref "E1") (pin "4") (pinfunction "C_4") (pintype "input"))
      (node (ref "E1") (pin "5") (pinfunction "D_5") (pintype "input"))
      (node (ref "E17") (pin "1") (pinfunction "1G_1") (pintype "input"))
      (node (ref "E17") (pin "15") (pinfunction "2G_15") (pintype "input"))
      (node (ref "E18") (pin "1") (pinfunction "1G_1") (pintype "input"))
      (node (ref "E18") (pin "15") (pinfunction "2G_15") (pintype "input"))
      (node (ref "E19") (pin "1") (pinfunction "1G_1") (pintype "input"))
      (node (ref "E19") (pin "15") (pinfunction "2G_15") (pintype "input"))
      (node (ref "E2") (pin "3") (pinfunction "B_3") (pintype "input"))
      (node (ref "E2") (pin "4") (pinfunction "C_4") (pintype "input"))
      (node (ref "E2") (pin "5") (pinfunction "D_5") (pintype "input"))
      (node (ref "E3") (pin "3") (pinfunction "B_3") (pintype "input"))
      (node (ref "E3") (pin "4") (pinfunction "C_4") (pintype "input"))
      (node (ref "E3") (pin "5") (pinfunction "D_5") (pintype "input"))
      (node (ref "GND") (pin "1") (pinfunction "P_1") (pintype "passive"))
      (node (ref "J1") (pin "11") (pinfunction "11_11") (pintype "passive"))
      (node (ref "J1") (pin "13") (pinfunction "13_13") (pintype "passive"))
      (node (ref "J1") (pin "15") (pinfunction "15_15") (pintype "passive"))
      (node (ref "J1") (pin "17") (pinfunction "17_17") (pintype "passive"))
      (node (ref "J1") (pin "19") (pinfunction "19_19") (pintype "passive"))
      (node (ref "J1") (pin "21") (pinfunction "21_21") (pintype "passive"))
      (node (ref "J1") (pin "23") (pinfunction "23_23") (pintype "passive"))
      (node (ref "J1") (pin "25") (pinfunction "25_25") (pintype "passive"))
      (node (ref "J1") (pin "27") (pinfunction "27_27") (pintype "passive"))
      (node (ref "J1") (pin "29") (pinfunction "29_29") (pintype "passive"))
      (node (ref "J1") (pin "31") (pinfunction "31_31") (pintype "passive"))
      (node (ref "J1") (pin "33") (pinfunction "33_33") (pintype "passive"))
      (node (ref "J1") (pin "35") (pinfunction "35_35") (pintype "passive"))
      (node (ref "J1") (pin "37") (pinfunction "37_37") (pintype "passive"))
      (node (ref "J1") (pin "39") (pinfunction "39_39") (pintype "passive"))
      (node (ref "J2") (pin "11") (pinfunction "11_11") (pintype "passive"))
      (node (ref "J2") (pin "13") (pinfunction "13_13") (pintype "passive"))
      (node (ref "J2") (pin "15") (pinfunction "15_15") (pintype "passive"))
      (node (ref "J2") (pin "16") (pinfunction "16_16") (pintype "passive"))
      (node (ref "J2") (pin "17") (pinfunction "17_17") (pintype "passive"))
      (node (ref "J2") (pin "19") (pinfunction "19_19") (pintype "passive"))
      (node (ref "J2") (pin "21") (pinfunction "21_21") (pintype "passive"))
      (node (ref "J2") (pin "23") (pinfunction "23_23") (pintype "passive"))
      (node (ref "J2") (pin "25") (pinfunction "25_25") (pintype "passive"))
      (node (ref "J2") (pin "27") (pinfunction "27_27") (pintype "passive"))
      (node (ref "J2") (pin "29") (pinfunction "29_29") (pintype "passive"))
      (node (ref "J2") (pin "31") (pinfunction "31_31") (pintype "passive"))
      (node (ref "J2") (pin "33") (pinfunction "33_33") (pintype "passive"))
      (node (ref "J2") (pin "35") (pinfunction "35_35") (pintype "passive"))
      (node (ref "J2") (pin "37") (pinfunction "37_37") (pintype "passive"))
      (node (ref "J2") (pin "39") (pinfunction "39_39") (pintype "passive"))
      (node (ref "J3") (pin "8") (pinfunction "8_8") (pintype "passive"))
      (node (ref "J4") (pin "8") (pinfunction "8_8") (pintype "passive"))
      (node (ref "R1") (pin "1") (pinfunction "1_1") (pintype "passive"))
      (node (ref "R17") (pin "1") (pinfunction "1_1") (pintype "passive"))
      (node (ref "R18") (pin "1") (pinfunction "1_1") (pintype "passive"))
      (node (ref "R19") (pin "1") (pinfunction "1_1") (pintype "passive"))
      (node (ref "R2") (pin "1") (pinfunction "1_1") (pintype "passive"))
      (node (ref "R20") (pin "1") (pinfunction "1_1") (pintype "passive"))
      (node (ref "R21") (pin "1") (pinfunction "1_1") (pintype "passive"))
      (node (ref "R22") (pin "1") (pinfunction "1_1") (pintype "passive"))
      (node (ref "R23") (pin "1") (pinfunction "1_1") (pintype "passive"))
      (node (ref "R24") (pin "1") (pinfunction "1_1") (pintype "passive"))
      (node (ref "R27") (pin "1") (pinfunction "1_1") (pintype "passive"))
      (node (ref "R3") (pin "1") (pinfunction "1_1") (pintype "passive"))
      (node (ref "R30") (pin "1") (pinfunction "1_1") (pintype "passive"))
      (node (ref "R4") (pin "1") (pinfunction "1_1") (pintype "passive"))
    )
    (net (code "33") (name "KEYSTB") (class "Default")
      (node (ref "E24") (pin "1") (pinfunction "I_1") (pintype "input"))
      (node (ref "E8") (pin "5") (pinfunction "I1_5") (pintype "input"))
      (node (ref "J4") (pin "2") (pinfunction "2_2") (pintype "passive"))
    )
    (net (code "34") (name "LDSR") (class "Default")
      (node (ref "E33") (pin "13") (pinfunction "O_13") (pintype "output"))
      (node (ref "E5") (pin "9") (pinfunction "CLK_9") (pintype "input"))
      (node (ref "E6") (pin "9") (pinfunction "CLK_9") (pintype "input"))
      (node (ref "E7") (pin "9") (pinfunction "CLK_9") (pintype "input"))
    )
    (net (code "35") (name "MH0") (class "Default")
      (node (ref "E20") (pin "9") (pinfunction "Q_9") (pintype "output"))
      (node (ref "E22") (pin "11") (pinfunction "I0_11") (pintype "input"))
      (node (ref "E8") (pin "13") (pinfunction "I1_13") (pintype "input"))
    )
    (net (code "36") (name "MPXA") (class "Default")
      (node (ref "E17") (pin "14") (pinfunction "A_14") (pintype "input"))
      (node (ref "E18") (pin "14") (pinfunction "A_14") (pintype "input"))
      (node (ref "E19") (pin "14") (pinfunction "A_14") (pintype "input"))
      (node (ref "J4") (pin "14") (pinfunction "14_14") (pintype "passive"))
    )
    (net (code "37") (name "MPXB") (class "Default")
      (node (ref "E17") (pin "2") (pinfunction "B_2") (pintype "input"))
      (node (ref "E18") (pin "2") (pinfunction "B_2") (pintype "input"))
      (node (ref "E19") (pin "2") (pinfunction "B_2") (pintype "input"))
      (node (ref "J4") (pin "13") (pinfunction "13_13") (pintype "passive"))
    )
    (net (code "38") (name "NUM") (class "Default")
      (node (ref "E16") (pin "12") (pinfunction "D_12") (pintype "input"))
      (node (ref "E21") (pin "13") (pinfunction "I2_13") (pintype "input"))
      (node (ref "E8") (pin "4") (pinfunction "I0_4") (pintype "input"))
      (node (ref "J4") (pin "11") (pinfunction "11_11") (pintype "passive"))
    )
    (net (code "39") (name "NUMCLK") (class "Default")
      (node (ref "E1") (pin "8") (pinfunction "CK2_8") (pintype "input"))
      (node (ref "E1") (pin "9") (pinfunction "CK1_9") (pintype "input"))
      (node (ref "E2") (pin "8") (pinfunction "CK2_8") (pintype "input"))
      (node (ref "E2") (pin "9") (pinfunction "CK1_9") (pintype "input"))
      (node (ref "E3") (pin "8") (pinfunction "CK2_8") (pintype "input"))
      (node (ref "E3") (pin "9") (pinfunction "CK1_9") (pintype "input"))
      (node (ref "E8") (pin "6") (pinfunction "O_6") (pintype "output"))
    )
    (net (code "40") (name "Net-(E1A-QB)") (class "Default")
      (node (ref "E1") (pin "12") (pinfunction "QB_12") (pintype "output"))
      (node (ref "E5") (pin "13") (pinfunction "D4_13") (pintype "input"))
      (node (ref "E9") (pin "8") (pinfunction "A4_8") (pintype "input"))
    )
    (net (code "41") (name "Net-(E1A-QC)") (class "Default")
      (node (ref "E1") (pin "11") (pinfunction "QC_11") (pintype "output"))
      (node (ref "E5") (pin "4") (pinfunction "D1_4") (pintype "input"))
      (node (ref "E9") (pin "2") (pinfunction "A1_2") (pintype "input"))
    )
    (net (code "42") (name "Net-(E1A-QD)") (class "Default")
      (node (ref "E1") (pin "10") (pinfunction "QD_10") (pintype "output"))
      (node (ref "E5") (pin "5") (pinfunction "D2_5") (pintype "input"))
      (node (ref "E9") (pin "4") (pinfunction "A2_4") (pintype "input"))
    )
    (net (code "43") (name "Net-(E4B-C)") (class "Default")
      (node (ref "C37") (pin "2") (pinfunction "2_2") (pintype "passive"))
      (node (ref "C40") (pin "2") (pinfunction "2_2") (pintype "passive"))
      (node (ref "E4") (pin "6") (pinfunction "C_6") (pintype "input"))
    )
    (net (code "44") (name "Net-(E4B-Q)") (class "Default")
      (node (ref "E4") (pin "5") (pinfunction "Q_5") (pintype "output"))
      (node (ref "E8") (pin "10") (pinfunction "I1_10") (pintype "input"))
      (node (ref "E8") (pin "12") (pinfunction "I0_12") (pintype "input"))
    )
    (net (code "45") (name "Net-(E4B-R{slash}C)") (class "Default")
      (node (ref "C37") (pin "1") (pinfunction "1_1") (pintype "passive"))
      (node (ref "C40") (pin "1") (pinfunction "1_1") (pintype "passive"))
      (node (ref "E4") (pin "7") (pinfunction "R/C_7") (pintype "input"))
      (node (ref "R25") (pin "2") (pinfunction "2_2") (pintype "passive"))
    )
    (net (code "46") (name "Net-(E5A-Q1)") (class "Default")
      (node (ref "E5") (pin "2") (pinfunction "Q1_2") (pintype "output"))
      (node (ref "E9") (pin "17") (pinfunction "A4_17") (pintype "input"))
    )
    (net (code "47") (name "Net-(E5A-Q2)") (class "Default")
      (node (ref "E5") (pin "7") (pinfunction "Q2_7") (pintype "output"))
      (node (ref "E9") (pin "15") (pinfunction "A3_15") (pintype "input"))
    )
    (net (code "48") (name "Net-(E5A-Q3)") (class "Default")
      (node (ref "E5") (pin "10") (pinfunction "Q3_10") (pintype "output"))
      (node (ref "E9") (pin "13") (pinfunction "A2_13") (pintype "input"))
    )
    (net (code "49") (name "Net-(E5A-Q4)") (class "Default")
      (node (ref "E5") (pin "15") (pinfunction "Q4_15") (pintype "output"))
      (node (ref "E9") (pin "11") (pinfunction "A1_11") (pintype "input"))
    )
    (net (code "50") (name "Net-(E10A-A1)") (class "Default")
      (node (ref "E10") (pin "2") (pinfunction "A1_2") (pintype "input"))
      (node (ref "E2") (pin "11") (pinfunction "QC_11") (pintype "output"))
      (node (ref "E6") (pin "4") (pinfunction "D1_4") (pintype "input"))
    )
    (net (code "51") (name "Net-(E10A-A2)") (class "Default")
      (node (ref "E10") (pin "4") (pinfunction "A2_4") (pintype "input"))
      (node (ref "E2") (pin "10") (pinfunction "QD_10") (pintype "output"))
      (node (ref "E6") (pin "5") (pinfunction "D2_5") (pintype "input"))
    )
    (net (code "52") (name "Net-(E10A-A4)") (class "Default")
      (node (ref "E10") (pin "8") (pinfunction "A4_8") (pintype "input"))
      (node (ref "E2") (pin "12") (pinfunction "QB_12") (pintype "output"))
      (node (ref "E6") (pin "13") (pinfunction "D4_13") (pintype "input"))
    )
    (net (code "53") (name "Net-(E10B-A1)") (class "Default")
      (node (ref "E10") (pin "11") (pinfunction "A1_11") (pintype "input"))
      (node (ref "E6") (pin "15") (pinfunction "Q4_15") (pintype "output"))
    )
    (net (code "54") (name "Net-(E10B-A2)") (class "Default")
      (node (ref "E10") (pin "13") (pinfunction "A2_13") (pintype "input"))
      (node (ref "E6") (pin "10") (pinfunction "Q3_10") (pintype "output"))
    )
    (net (code "55") (name "Net-(E10B-A3)") (class "Default")
      (node (ref "E10") (pin "15") (pinfunction "A3_15") (pintype "input"))
      (node (ref "E6") (pin "7") (pinfunction "Q2_7") (pintype "output"))
    )
    (net (code "56") (name "Net-(E10B-A4)") (class "Default")
      (node (ref "E10") (pin "17") (pinfunction "A4_17") (pintype "input"))
      (node (ref "E6") (pin "2") (pinfunction "Q1_2") (pintype "output"))
    )
    (net (code "57") (name "Net-(E11A-A1)") (class "Default")
      (node (ref "E11") (pin "2") (pinfunction "A1_2") (pintype "input"))
      (node (ref "E3") (pin "11") (pinfunction "QC_11") (pintype "output"))
      (node (ref "E7") (pin "4") (pinfunction "D1_4") (pintype "input"))
    )
    (net (code "58") (name "Net-(E11A-A2)") (class "Default")
      (node (ref "E11") (pin "4") (pinfunction "A2_4") (pintype "input"))
      (node (ref "E3") (pin "10") (pinfunction "QD_10") (pintype "output"))
      (node (ref "E7") (pin "5") (pinfunction "D2_5") (pintype "input"))
    )
    (net (code "59") (name "Net-(E11A-A4)") (class "Default")
      (node (ref "E11") (pin "8") (pinfunction "A4_8") (pintype "input"))
      (node (ref "E3") (pin "12") (pinfunction "QB_12") (pintype "output"))
      (node (ref "E7") (pin "13") (pinfunction "D4_13") (pintype "input"))
    )
    (net (code "60") (name "Net-(E11B-A1)") (class "Default")
      (node (ref "E11") (pin "11") (pinfunction "A1_11") (pintype "input"))
      (node (ref "E7") (pin "15") (pinfunction "Q4_15") (pintype "output"))
    )
    (net (code "61") (name "Net-(E11B-A2)") (class "Default")
      (node (ref "E11") (pin "13") (pinfunction "A2_13") (pintype "input"))
      (node (ref "E7") (pin "10") (pinfunction "Q3_10") (pintype "output"))
    )
    (net (code "62") (name "Net-(E11B-A3)") (class "Default")
      (node (ref "E11") (pin "15") (pinfunction "A3_15") (pintype "input"))
      (node (ref "E7") (pin "7") (pinfunction "Q2_7") (pintype "output"))
    )
    (net (code "63") (name "Net-(E11B-A4)") (class "Default")
      (node (ref "E11") (pin "17") (pinfunction "A4_17") (pintype "input"))
      (node (ref "E7") (pin "2") (pinfunction "Q1_2") (pintype "output"))
    )
    (net (code "64") (name "Net-(E12A-Q1)") (class "Default")
      (node (ref "E12") (pin "2") (pinfunction "Q1_2") (pintype "output"))
      (node (ref "E17") (pin "4") (pinfunction "1C2_4") (pintype "input"))
    )
    (net (code "65") (name "Net-(E12A-Q2)") (class "Default")
      (node (ref "E12") (pin "5") (pinfunction "Q2_5") (pintype "output"))
      (node (ref "E17") (pin "6") (pinfunction "1C0_6") (pintype "input"))
    )
    (net (code "66") (name "Net-(E12A-Q3)") (class "Default")
      (node (ref "E12") (pin "7") (pinfunction "Q3_7") (pintype "output"))
      (node (ref "E17") (pin "13") (pinfunction "2C3_13") (pintype "input"))
    )
    (net (code "67") (name "Net-(E12A-Q4)") (class "Default")
      (node (ref "E12") (pin "10") (pinfunction "Q4_10") (pintype "output"))
      (node (ref "E17") (pin "11") (pinfunction "2C1_11") (pintype "input"))
    )
    (net (code "68") (name "Net-(E12A-Q5)") (class "Default")
      (node (ref "E12") (pin "12") (pinfunction "Q5_12") (pintype "output"))
      (node (ref "E17") (pin "12") (pinfunction "2C2_12") (pintype "input"))
    )
    (net (code "69") (name "Net-(E12A-Q6)") (class "Default")
      (node (ref "E12") (pin "15") (pinfunction "Q6_15") (pintype "output"))
      (node (ref "E17") (pin "10") (pinfunction "2C0_10") (pintype "input"))
    )
    (net (code "70") (name "Net-(E13A-Q1)") (class "Default")
      (node (ref "E13") (pin "2") (pinfunction "Q1_2") (pintype "output"))
      (node (ref "E19") (pin "12") (pinfunction "2C2_12") (pintype "input"))
    )
    (net (code "71") (name "Net-(E13A-Q2)") (class "Default")
      (node (ref "E13") (pin "5") (pinfunction "Q2_5") (pintype "output"))
      (node (ref "E19") (pin "10") (pinfunction "2C0_10") (pintype "input"))
    )
    (net (code "72") (name "Net-(E13A-Q3)") (class "Default")
      (node (ref "E13") (pin "7") (pinfunction "Q3_7") (pintype "output"))
      (node (ref "E18") (pin "3") (pinfunction "1C3_3") (pintype "input"))
    )
    (net (code "73") (name "Net-(E13A-Q4)") (class "Default")
      (node (ref "E13") (pin "10") (pinfunction "Q4_10") (pintype "output"))
      (node (ref "E18") (pin "5") (pinfunction "1C1_5") (pintype "input"))
    )
    (net (code "74") (name "Net-(E13A-Q5)") (class "Default")
      (node (ref "E13") (pin "12") (pinfunction "Q5_12") (pintype "output"))
      (node (ref "E18") (pin "4") (pinfunction "1C2_4") (pintype "input"))
    )
    (net (code "75") (name "Net-(E13A-Q6)") (class "Default")
      (node (ref "E13") (pin "15") (pinfunction "Q6_15") (pintype "output"))
      (node (ref "E18") (pin "6") (pinfunction "1C0_6") (pintype "input"))
    )
    (net (code "76") (name "Net-(E14A-Q1)") (class "Default")
      (node (ref "E14") (pin "2") (pinfunction "Q1_2") (pintype "output"))
      (node (ref "E18") (pin "13") (pinfunction "2C3_13") (pintype "input"))
    )
    (net (code "77") (name "Net-(E14A-Q2)") (class "Default")
      (node (ref "E14") (pin "5") (pinfunction "Q2_5") (pintype "output"))
      (node (ref "E18") (pin "11") (pinfunction "2C1_11") (pintype "input"))
    )
    (net (code "78") (name "Net-(E14A-Q3)") (class "Default")
      (node (ref "E14") (pin "7") (pinfunction "Q3_7") (pintype "output"))
      (node (ref "E18") (pin "12") (pinfunction "2C2_12") (pintype "input"))
    )
    (net (code "79") (name "Net-(E14A-Q4)") (class "Default")
      (node (ref "E14") (pin "10") (pinfunction "Q4_10") (pintype "output"))
      (node (ref "E18") (pin "10") (pinfunction "2C0_10") (pintype "input"))
    )
    (net (code "80") (name "Net-(E14A-Q5)") (class "Default")
      (node (ref "E14") (pin "12") (pinfunction "Q5_12") (pintype "output"))
      (node (ref "E17") (pin "3") (pinfunction "1C3_3") (pintype "input"))
    )
    (net (code "81") (name "Net-(E14A-Q6)") (class "Default")
      (node (ref "E14") (pin "15") (pinfunction "Q6_15") (pintype "output"))
      (node (ref "E17") (pin "5") (pinfunction "1C1_5") (pintype "input"))
    )
    (net (code "82") (name "Net-(E15A-Q1)") (class "Default")
      (node (ref "E15") (pin "2") (pinfunction "Q1_2") (pintype "output"))
      (node (ref "E19") (pin "3") (pinfunction "1C3_3") (pintype "input"))
    )
    (net (code "83") (name "Net-(E15A-Q2)") (class "Default")
      (node (ref "E15") (pin "5") (pinfunction "Q2_5") (pintype "output"))
      (node (ref "E19") (pin "5") (pinfunction "1C1_5") (pintype "input"))
    )
    (net (code "84") (name "Net-(E15A-Q3)") (class "Default")
      (node (ref "E15") (pin "7") (pinfunction "Q3_7") (pintype "output"))
      (node (ref "E19") (pin "4") (pinfunction "1C2_4") (pintype "input"))
    )
    (net (code "85") (name "Net-(E15A-Q4)") (class "Default")
      (node (ref "E15") (pin "10") (pinfunction "Q4_10") (pintype "output"))
      (node (ref "E19") (pin "6") (pinfunction "1C0_6") (pintype "input"))
    )
    (net (code "86") (name "Net-(E15A-Q5)") (class "Default")
      (node (ref "E15") (pin "12") (pinfunction "Q5_12") (pintype "output"))
      (node (ref "E19") (pin "13") (pinfunction "2C3_13") (pintype "input"))
    )
    (net (code "87") (name "Net-(E15A-Q6)") (class "Default")
      (node (ref "E15") (pin "15") (pinfunction "Q6_15") (pintype "output"))
      (node (ref "E19") (pin "11") (pinfunction "2C1_11") (pintype "input"))
    )
    (net (code "88") (name "Net-(E16A-CLK)") (class "Default")
      (node (ref "E16") (pin "3") (pinfunction "CLK_3") (pintype "input"))
      (node (ref "E21") (pin "12") (pinfunction "O_12") (pintype "output"))
    )
    (net (code "89") (name "Net-(E20A-PRE)") (class "Default")
      (node (ref "E20") (pin "4") (pinfunction "PRE_4") (pintype "input"))
      (node (ref "E26") (pin "8") (pinfunction "~{Q4}_8") (pintype "output"))
    )
    (net (code "90") (name "Net-(E20B-CLK)") (class "Default")
      (node (ref "E20") (pin "11") (pinfunction "CLK_11") (pintype "input"))
      (node (ref "E22") (pin "1") (pinfunction "O_1") (pintype "output"))
      (node (ref "E4") (pin "9") (pinfunction "A_9") (pintype "input"))
    )
    (net (code "91") (name "Net-(E21A-I0)") (class "Default")
      (node (ref "E21") (pin "1") (pinfunction "I0_1") (pintype "input"))
      (node (ref "E24") (pin "4") (pinfunction "O_4") (pintype "output"))
    )
    (net (code "92") (name "Net-(E21B-I0)") (class "Default")
      (node (ref "E21") (pin "3") (pinfunction "I0_3") (pintype "input"))
      (node (ref "E21") (pin "4") (pinfunction "I1_4") (pintype "input"))
      (node (ref "E22") (pin "4") (pinfunction "O_4") (pintype "output"))
    )
    (net (code "93") (name "Net-(E21C-O)") (class "Default")
      (node (ref "E21") (pin "8") (pinfunction "O_8") (pintype "output"))
      (node (ref "E23") (pin "9") (pinfunction "I_9") (pintype "input"))
    )
    (net (code "94") (name "Net-(E22A-I0)") (class "Default")
      (node (ref "E22") (pin "2") (pinfunction "I0_2") (pintype "input"))
      (node (ref "E32") (pin "6") (pinfunction "O_6") (pintype "output"))
    )
    (net (code "95") (name "Net-(E22A-I1)") (class "Default")
      (node (ref "E22") (pin "3") (pinfunction "I1_3") (pintype "input"))
      (node (ref "E33") (pin "1") (pinfunction "O_1") (pintype "output"))
    )
    (net (code "96") (name "Net-(E22B-I0)") (class "Default")
      (node (ref "E22") (pin "5") (pinfunction "I0_5") (pintype "input"))
      (node (ref "E8") (pin "3") (pinfunction "O_3") (pintype "output"))
    )
    (net (code "97") (name "Net-(E22C-I0)") (class "Default")
      (node (ref "E22") (pin "8") (pinfunction "I0_8") (pintype "input"))
      (node (ref "E25") (pin "12") (pinfunction "O_12") (pintype "output"))
    )
    (net (code "98") (name "Net-(E22C-I1)") (class "Default")
      (node (ref "E22") (pin "9") (pinfunction "I1_9") (pintype "input"))
      (node (ref "E25") (pin "8") (pinfunction "O_8") (pintype "output"))
    )
    (net (code "99") (name "Net-(E22C-O)") (class "Default")
      (node (ref "E22") (pin "10") (pinfunction "O_10") (pintype "output"))
      (node (ref "E29") (pin "4") (pinfunction "G2A_4") (pintype "input"))
      (node (ref "E29") (pin "5") (pinfunction "G2B_5") (pintype "input"))
      (node (ref "E31") (pin "15") (pinfunction "2G_15") (pintype "input"))
    )
    (net (code "100") (name "Net-(E22D-O)") (class "Default")
      (node (ref "E22") (pin "13") (pinfunction "O_13") (pintype "output"))
      (node (ref "E30") (pin "4") (pinfunction "I0_4") (pintype "input"))
    )
    (net (code "101") (name "Net-(E23A-I)") (class "Default")
      (node (ref "E23") (pin "1") (pinfunction "I_1") (pintype "input"))
      (node (ref "E33") (pin "4") (pinfunction "O_4") (pintype "output"))
    )
    (net (code "102") (name "Net-(E23E-I)") (class "Default")
      (node (ref "E23") (pin "11") (pinfunction "I_11") (pintype "input"))
      (node (ref "E24") (pin "10") (pinfunction "O_10") (pintype "output"))
    )
    (net (code "103") (name "Net-(E24D-O)") (class "Default")
      (node (ref "E24") (pin "8") (pinfunction "O_8") (pintype "output"))
      (node (ref "E32") (pin "5") (pinfunction "I1_5") (pintype "input"))
    )
    (net (code "104") (name "Net-(E24F-O)") (class "Default")
      (node (ref "E24") (pin "12") (pinfunction "O_12") (pintype "output"))
      (node (ref "E25") (pin "10") (pinfunction "I1_10") (pintype "input"))
      (node (ref "E28") (pin "1") (pinfunction "1G_1") (pintype "input"))
      (node (ref "E28") (pin "15") (pinfunction "2G_15") (pintype "input"))
      (node (ref "E33") (pin "6") (pinfunction "I1_6") (pintype "input"))
    )
    (net (code "105") (name "Net-(E25A-I0)") (class "Default")
      (node (ref "E25") (pin "1") (pinfunction "I0_1") (pintype "input"))
      (node (ref "E26") (pin "16") (pinfunction "Q1_16") (pintype "output"))
      (node (ref "E29") (pin "3") (pinfunction "C_3") (pintype "input"))
    )
    (net (code "106") (name "Net-(E25A-I2)") (class "Default")
      (node (ref "E25") (pin "13") (pinfunction "I2_13") (pintype "input"))
      (node (ref "E26") (pin "15") (pinfunction "Q2_15") (pintype "output"))
      (node (ref "E27") (pin "3") (pinfunction "I_3") (pintype "input"))
      (node (ref "E29") (pin "2") (pinfunction "B_2") (pintype "input"))
      (node (ref "E30") (pin "1") (pinfunction "I0_1") (pintype "input"))
    )
    (net (code "107") (name "Net-(E25C-I0)") (class "Default")
      (node (ref "E25") (pin "9") (pinfunction "I0_9") (pintype "input"))
      (node (ref "E26") (pin "9") (pinfunction "Q4_9") (pintype "output"))
    )
    (net (code "108") (name "Net-(E26A-Q3)") (class "Default")
      (node (ref "E26") (pin "10") (pinfunction "Q3_10") (pintype "output"))
      (node (ref "E29") (pin "1") (pinfunction "A_1") (pintype "input"))
    )
    (net (code "109") (name "Net-(E27A-O)") (class "Default")
      (node (ref "E27") (pin "2") (pinfunction "O_2") (pintype "output"))
      (node (ref "E30") (pin "12") (pinfunction "I0_12") (pintype "input"))
    )
    (net (code "110") (name "Net-(E27B-O)") (class "Default")
      (node (ref "E27") (pin "4") (pinfunction "O_4") (pintype "output"))
      (node (ref "E31") (pin "12") (pinfunction "2A1_12") (pintype "input"))
    )
    (net (code "111") (name "Net-(E27C-O)") (class "Default")
      (node (ref "E27") (pin "6") (pinfunction "O_6") (pintype "output"))
      (node (ref "E30") (pin "13") (pinfunction "I1_13") (pintype "input"))
    )
    (net (code "112") (name "Net-(E28A-1A1)") (class "Default")
      (node (ref "E28") (pin "2") (pinfunction "1A1_2") (pintype "input"))
      (node (ref "E29") (pin "9") (pinfunction "Y6_9") (pintype "output"))
      (node (ref "E32") (pin "2") (pinfunction "I1_2") (pintype "input"))
    )
    (net (code "113") (name "Net-(E28A-1A2)") (class "Default")
      (node (ref "E28") (pin "4") (pinfunction "1A2_4") (pintype "input"))
      (node (ref "E29") (pin "7") (pinfunction "Y7_7") (pintype "output"))
      (node (ref "E30") (pin "10") (pinfunction "I1_10") (pintype "input"))
      (node (ref "E32") (pin "1") (pinfunction "I0_1") (pintype "input"))
    )
    (net (code "114") (name "Net-(E28A-1A3)") (class "Default")
      (node (ref "E28") (pin "6") (pinfunction "1A3_6") (pintype "input"))
      (node (ref "E30") (pin "9") (pinfunction "I0_9") (pintype "input"))
      (node (ref "E31") (pin "6") (pinfunction "1A3_6") (pintype "input"))
      (node (ref "E32") (pin "8") (pinfunction "O_8") (pintype "output"))
      (node (ref "E33") (pin "5") (pinfunction "I0_5") (pintype "input"))
    )
    (net (code "115") (name "Net-(E28A-2A2)") (class "Default")
      (node (ref "E28") (pin "14") (pinfunction "2A2_14") (pintype "input"))
      (node (ref "E30") (pin "11") (pinfunction "O_11") (pintype "output"))
    )
    (net (code "116") (name "Net-(E29A-Y0)") (class "Default")
      (node (ref "E29") (pin "15") (pinfunction "Y0_15") (pintype "output"))
      (node (ref "E33") (pin "8") (pinfunction "I0_8") (pintype "input"))
    )
    (net (code "117") (name "Net-(E29A-Y1)") (class "Default")
      (node (ref "E29") (pin "14") (pinfunction "Y1_14") (pintype "output"))
      (node (ref "E33") (pin "12") (pinfunction "I1_12") (pintype "input"))
    )
    (net (code "118") (name "Net-(E29A-Y2)") (class "Default")
      (node (ref "E29") (pin "13") (pinfunction "Y2_13") (pintype "output"))
      (node (ref "E30") (pin "2") (pinfunction "I1_2") (pintype "input"))
      (node (ref "E32") (pin "10") (pinfunction "I1_10") (pintype "input"))
    )
    (net (code "119") (name "Net-(E29A-Y3)") (class "Default")
      (node (ref "E29") (pin "12") (pinfunction "Y3_12") (pintype "output"))
      (node (ref "E32") (pin "9") (pinfunction "I0_9") (pintype "input"))
    )
    (net (code "120") (name "Net-(E29A-Y4)") (class "Default")
      (node (ref "E29") (pin "11") (pinfunction "Y4_11") (pintype "output"))
      (node (ref "E31") (pin "10") (pinfunction "1A4_10") (pintype "input"))
    )
    (net (code "121") (name "Net-(E29A-Y5)") (class "Default")
      (node (ref "E29") (pin "10") (pinfunction "Y5_10") (pintype "output"))
      (node (ref "E31") (pin "2") (pinfunction "1A1_2") (pintype "input"))
    )
    (net (code "122") (name "Net-(E30A-O)") (class "Default")
      (node (ref "E30") (pin "3") (pinfunction "O_3") (pintype "output"))
      (node (ref "E31") (pin "14") (pinfunction "2A2_14") (pintype "input"))
    )
    (net (code "123") (name "Net-(E30B-O)") (class "Default")
      (node (ref "E30") (pin "6") (pinfunction "O_6") (pintype "output"))
      (node (ref "E34") (pin "1") (pinfunction "1G_1") (pintype "input"))
      (node (ref "E34") (pin "15") (pinfunction "2G_15") (pintype "input"))
      (node (ref "E35") (pin "4") (pinfunction "G2A_4") (pintype "input"))
      (node (ref "E35") (pin "5") (pinfunction "G2B_5") (pintype "input"))
    )
    (net (code "124") (name "Net-(E31A-1A2)") (class "Default")
      (node (ref "E31") (pin "4") (pinfunction "1A2_4") (pintype "input"))
      (node (ref "E32") (pin "3") (pinfunction "O_3") (pintype "output"))
    )
    (net (code "125") (name "Net-(E32D-I0)") (class "Default")
      (node (ref "E32") (pin "12") (pinfunction "I0_12") (pintype "input"))
      (node (ref "E35") (pin "11") (pinfunction "Y4_11") (pintype "output"))
    )
    (net (code "126") (name "Net-(E33C-O)") (class "Default")
      (node (ref "E33") (pin "10") (pinfunction "O_10") (pintype "output"))
      (node (ref "E36") (pin "9") (pinfunction "CLK_9") (pintype "input"))
    )
    (net (code "127") (name "Net-(E34A-1A3)") (class "Default")
      (node (ref "E34") (pin "6") (pinfunction "1A3_6") (pintype "input"))
      (node (ref "E35") (pin "9") (pinfunction "Y6_9") (pintype "output"))
    )
    (net (code "128") (name "Net-(E34A-2A1)") (class "Default")
      (node (ref "E34") (pin "12") (pinfunction "2A1_12") (pintype "input"))
      (node (ref "E35") (pin "10") (pinfunction "Y5_10") (pintype "output"))
    )
    (net (code "129") (name "POWCK") (class "Default")
      (node (ref "E24") (pin "11") (pinfunction "I_11") (pintype "input"))
      (node (ref "J2") (pin "28") (pinfunction "28_28") (pintype "passive"))
      (node (ref "R33") (pin "1") (pinfunction "1_1") (pintype "passive"))
    )
    (net (code "130") (name "THIS") (class "Default")
      (node (ref "E20") (pin "5") (pinfunction "Q_5") (pintype "output"))
      (node (ref "E28") (pin "12") (pinfunction "2A1_12") (pintype "input"))
    )
    (net (code "131") (name "VCC") (class "Default")
      (node (ref "C1") (pin "1") (pinfunction "1_1") (pintype "passive"))
      (node (ref "C10") (pin "1") (pinfunction "1_1") (pintype "passive"))
      (node (ref "C11") (pin "1") (pinfunction "1_1") (pintype "passive"))
      (node (ref "C12") (pin "1") (pinfunction "1_1") (pintype "passive"))
      (node (ref "C13") (pin "1") (pinfunction "1_1") (pintype "passive"))
      (node (ref "C14") (pin "1") (pinfunction "1_1") (pintype "passive"))
      (node (ref "C15") (pin "1") (pinfunction "1_1") (pintype "passive"))
      (node (ref "C16") (pin "1") (pinfunction "1_1") (pintype "passive"))
      (node (ref "C17") (pin "1") (pinfunction "1_1") (pintype "passive"))
      (node (ref "C18") (pin "1") (pinfunction "1_1") (pintype "passive"))
      (node (ref "C19") (pin "1") (pinfunction "1_1") (pintype "passive"))
      (node (ref "C2") (pin "1") (pinfunction "1_1") (pintype "passive"))
      (node (ref "C20") (pin "1") (pinfunction "1_1") (pintype "passive"))
      (node (ref "C21") (pin "1") (pinfunction "1_1") (pintype "passive"))
      (node (ref "C22") (pin "1") (pinfunction "1_1") (pintype "passive"))
      (node (ref "C23") (pin "1") (pinfunction "1_1") (pintype "passive"))
      (node (ref "C24") (pin "1") (pinfunction "1_1") (pintype "passive"))
      (node (ref "C25") (pin "1") (pinfunction "1_1") (pintype "passive"))
      (node (ref "C26") (pin "1") (pinfunction "1_1") (pintype "passive"))
      (node (ref "C27") (pin "1") (pinfunction "1_1") (pintype "passive"))
      (node (ref "C28") (pin "1") (pinfunction "1_1") (pintype "passive"))
      (node (ref "C29") (pin "1") (pinfunction "1_1") (pintype "passive"))
      (node (ref "C3") (pin "1") (pinfunction "1_1") (pintype "passive"))
      (node (ref "C30") (pin "1") (pinfunction "1_1") (pintype "passive"))
      (node (ref "C31") (pin "1") (pinfunction "1_1") (pintype "passive"))
      (node (ref "C32") (pin "1") (pinfunction "1_1") (pintype "passive"))
      (node (ref "C33") (pin "1") (pinfunction "1_1") (pintype "passive"))
      (node (ref "C34") (pin "1") (pinfunction "1_1") (pintype "passive"))
      (node (ref "C35") (pin "1") (pinfunction "1_1") (pintype "passive"))
      (node (ref "C36") (pin "1") (pinfunction "1_1") (pintype "passive"))
      (node (ref "C38") (pin "+") (pinfunction "+_+") (pintype "passive"))
      (node (ref "C39") (pin "+") (pinfunction "+_+") (pintype "passive"))
      (node (ref "C4") (pin "1") (pinfunction "1_1") (pintype "passive"))
      (node (ref "C5") (pin "1") (pinfunction "1_1") (pintype "passive"))
      (node (ref "C6") (pin "1") (pinfunction "1_1") (pintype "passive"))
      (node (ref "C7") (pin "1") (pinfunction "1_1") (pintype "passive"))
      (node (ref "C8") (pin "1") (pinfunction "1_1") (pintype "passive"))
      (node (ref "C9") (pin "1") (pinfunction "1_1") (pintype "passive"))
      (node (ref "E16") (pin "10") (pinfunction "PRE_10") (pintype "input"))
      (node (ref "E16") (pin "4") (pinfunction "PRE_4") (pintype "input"))
      (node (ref "E20") (pin "10") (pinfunction "PRE_10") (pintype "input"))
      (node (ref "E29") (pin "6") (pinfunction "G1_6") (pintype "input"))
      (node (ref "E34") (pin "10") (pinfunction "1A4_10") (pintype "input"))
      (node (ref "E35") (pin "6") (pinfunction "G1_6") (pintype "input"))
      (node (ref "E36") (pin "1") (pinfunction "CLR_1") (pintype "input"))
      (node (ref "E36") (pin "11") (pinfunction "D4_11") (pintype "input"))
      (node (ref "E36") (pin "13") (pinfunction "D5_13") (pintype "input"))
      (node (ref "E36") (pin "6") (pinfunction "D3_6") (pintype "input"))
      (node (ref "E4") (pin "10") (pinfunction "B_10") (pintype "input"))
      (node (ref "E4") (pin "11") (pinfunction "CLR_11") (pintype "input"))
      (node (ref "J1") (pin "1") (pinfunction "1_1") (pintype "passive"))
      (node (ref "J1") (pin "2") (pinfunction "2_2") (pintype "passive"))
      (node (ref "J1") (pin "3") (pinfunction "3_3") (pintype "passive"))
      (node (ref "J1") (pin "4") (pinfunction "4_4") (pintype "passive"))
      (node (ref "J1") (pin "5") (pinfunction "5_5") (pintype "passive"))
      (node (ref "J1") (pin "7") (pinfunction "7_7") (pintype "passive"))
      (node (ref "J1") (pin "9") (pinfunction "9_9") (pintype "passive"))
      (node (ref "J2") (pin "1") (pinfunction "1_1") (pintype "passive"))
      (node (ref "J2") (pin "3") (pinfunction "3_3") (pintype "passive"))
      (node (ref "J2") (pin "5") (pinfunction "5_5") (pintype "passive"))
      (node (ref "J2") (pin "7") (pinfunction "7_7") (pintype "passive"))
      (node (ref "J2") (pin "9") (pinfunction "9_9") (pintype "passive"))
      (node (ref "J3") (pin "16") (pinfunction "16_16") (pintype "passive"))
      (node (ref "J4") (pin "16") (pinfunction "16_16") (pintype "passive"))
      (node (ref "R10") (pin "2") (pinfunction "2_2") (pintype "passive"))
      (node (ref "R11") (pin "2") (pinfunction "2_2") (pintype "passive"))
      (node (ref "R12") (pin "2") (pinfunction "2_2") (pintype "passive"))
      (node (ref "R13") (pin "2") (pinfunction "2_2") (pintype "passive"))
      (node (ref "R14") (pin "2") (pinfunction "2_2") (pintype "passive"))
      (node (ref "R15") (pin "2") (pinfunction "2_2") (pintype "passive"))
      (node (ref "R16") (pin "2") (pinfunction "2_2") (pintype "passive"))
      (node (ref "R25") (pin "1") (pinfunction "1_1") (pintype "passive"))
      (node (ref "R26") (pin "2") (pinfunction "2_2") (pintype "passive"))
      (node (ref "R28") (pin "2") (pinfunction "2_2") (pintype "passive"))
      (node (ref "R29") (pin "2") (pinfunction "2_2") (pintype "passive"))
      (node (ref "R31") (pin "2") (pinfunction "2_2") (pintype "passive"))
      (node (ref "R32") (pin "2") (pinfunction "2_2") (pintype "passive"))
      (node (ref "R33") (pin "2") (pinfunction "2_2") (pintype "passive"))
      (node (ref "R34") (pin "1") (pinfunction "1_1") (pintype "passive"))
      (node (ref "R35") (pin "1") (pinfunction "1_1") (pintype "passive"))
      (node (ref "R36") (pin "1") (pinfunction "1_1") (pintype "passive"))
      (node (ref "R5") (pin "2") (pinfunction "2_2") (pintype "passive"))
      (node (ref "R6") (pin "2") (pinfunction "2_2") (pintype "passive"))
      (node (ref "R7") (pin "2") (pinfunction "2_2") (pintype "passive"))
      (node (ref "R8") (pin "2") (pinfunction "2_2") (pintype "passive"))
      (node (ref "R9") (pin "2") (pinfunction "2_2") (pintype "passive"))
      (node (ref "VCC") (pin "1") (pinfunction "P_1") (pintype "passive"))
    )
    (net (code "132") (name "unconnected-(E4B-~{Q}-Pad12)") (class "Default")
      (node (ref "E4") (pin "12") (pinfunction "~{Q}_12") (pintype "output"))
    )
    (net (code "133") (name "unconnected-(E5A-~{Q1}-Pad3)") (class "Default")
      (node (ref "E5") (pin "3") (pinfunction "~{Q1}_3") (pintype "output"))
    )
    (net (code "134") (name "unconnected-(E5A-~{Q2}-Pad6)") (class "Default")
      (node (ref "E5") (pin "6") (pinfunction "~{Q2}_6") (pintype "output"))
    )
    (net (code "135") (name "unconnected-(E5A-~{Q3}-Pad11)") (class "Default")
      (node (ref "E5") (pin "11") (pinfunction "~{Q3}_11") (pintype "output"))
    )
    (net (code "136") (name "unconnected-(E5A-~{Q4}-Pad14)") (class "Default")
      (node (ref "E5") (pin "14") (pinfunction "~{Q4}_14") (pintype "output"))
    )
    (net (code "137") (name "unconnected-(E6A-~{Q1}-Pad3)") (class "Default")
      (node (ref "E6") (pin "3") (pinfunction "~{Q1}_3") (pintype "output"))
    )
    (net (code "138") (name "unconnected-(E6A-~{Q2}-Pad6)") (class "Default")
      (node (ref "E6") (pin "6") (pinfunction "~{Q2}_6") (pintype "output"))
    )
    (net (code "139") (name "unconnected-(E6A-~{Q3}-Pad11)") (class "Default")
      (node (ref "E6") (pin "11") (pinfunction "~{Q3}_11") (pintype "output"))
    )
    (net (code "140") (name "unconnected-(E6A-~{Q4}-Pad14)") (class "Default")
      (node (ref "E6") (pin "14") (pinfunction "~{Q4}_14") (pintype "output"))
    )
    (net (code "141") (name "unconnected-(E7A-~{Q1}-Pad3)") (class "Default")
      (node (ref "E7") (pin "3") (pinfunction "~{Q1}_3") (pintype "output"))
    )
    (net (code "142") (name "unconnected-(E7A-~{Q2}-Pad6)") (class "Default")
      (node (ref "E7") (pin "6") (pinfunction "~{Q2}_6") (pintype "output"))
    )
    (net (code "143") (name "unconnected-(E7A-~{Q3}-Pad11)") (class "Default")
      (node (ref "E7") (pin "11") (pinfunction "~{Q3}_11") (pintype "output"))
    )
    (net (code "144") (name "unconnected-(E7A-~{Q4}-Pad14)") (class "Default")
      (node (ref "E7") (pin "14") (pinfunction "~{Q4}_14") (pintype "output"))
    )
    (net (code "145") (name "unconnected-(E16A-Q-Pad5)") (class "Default")
      (node (ref "E16") (pin "5") (pinfunction "Q_5") (pintype "output"))
    )
    (net (code "146") (name "unconnected-(E20A-~{Q}-Pad6)") (class "Default")
      (node (ref "E20") (pin "6") (pinfunction "~{Q}_6") (pintype "output"))
    )
    (net (code "147") (name "unconnected-(E26A-~{Q1}-Pad1)") (class "Default")
      (node (ref "E26") (pin "1") (pinfunction "~{Q1}_1") (pintype "output"))
    )
    (net (code "148") (name "unconnected-(E26A-~{Q2}-Pad14)") (class "Default")
      (node (ref "E26") (pin "14") (pinfunction "~{Q2}_14") (pintype "output"))
    )
    (net (code "149") (name "unconnected-(E26A-~{Q3}-Pad11)") (class "Default")
      (node (ref "E26") (pin "11") (pinfunction "~{Q3}_11") (pintype "output"))
    )
    (net (code "150") (name "unconnected-(E34A-1Y4-Pad9)") (class "Default")
      (node (ref "E34") (pin "9") (pinfunction "1Y4_9") (pintype "tri_state"))
    )
    (net (code "151") (name "unconnected-(E35A-Y0-Pad15)") (class "Default")
      (node (ref "E35") (pin "15") (pinfunction "Y0_15") (pintype "output"))
    )
    (net (code "152") (name "unconnected-(E35A-Y1-Pad14)") (class "Default")
      (node (ref "E35") (pin "14") (pinfunction "Y1_14") (pintype "output"))
    )
    (net (code "153") (name "unconnected-(E35A-Y2-Pad13)") (class "Default")
      (node (ref "E35") (pin "13") (pinfunction "Y2_13") (pintype "output"))
    )
    (net (code "154") (name "unconnected-(E35A-Y3-Pad12)") (class "Default")
      (node (ref "E35") (pin "12") (pinfunction "Y3_12") (pintype "output"))
    )
    (net (code "155") (name "unconnected-(E35A-Y7-Pad7)") (class "Default")
      (node (ref "E35") (pin "7") (pinfunction "Y7_7") (pintype "output"))
    )
    (net (code "156") (name "unconnected-(E36A-Q3-Pad7)") (class "Default")
      (node (ref "E36") (pin "7") (pinfunction "Q3_7") (pintype "output"))
    )
    (net (code "157") (name "unconnected-(E36A-Q4-Pad10)") (class "Default")
      (node (ref "E36") (pin "10") (pinfunction "Q4_10") (pintype "output"))
    )
    (net (code "158") (name "unconnected-(E36A-Q5-Pad12)") (class "Default")
      (node (ref "E36") (pin "12") (pinfunction "Q5_12") (pintype "output"))
    )
    (net (code "159") (name "~{ADRLTH}") (class "Default")
      (node (ref "E12") (pin "9") (pinfunction "CLK_9") (pintype "input"))
      (node (ref "E14") (pin "9") (pinfunction "CLK_9") (pintype "input"))
      (node (ref "E8") (pin "11") (pinfunction "O_11") (pintype "output"))
    )
    (net (code "160") (name "~{BFSW}") (class "Default")
      (node (ref "E28") (pin "9") (pinfunction "1Y4_9") (pintype "tri_state"))
      (node (ref "J2") (pin "24") (pinfunction "24_24") (pintype "passive"))
    )
    (net (code "161") (name "~{BKDTACNTL}") (class "Default")
      (node (ref "E28") (pin "3") (pinfunction "1Y1_3") (pintype "tri_state"))
      (node (ref "J2") (pin "12") (pinfunction "12_12") (pintype "passive"))
    )
    (net (code "162") (name "~{BOOTF}") (class "Default")
      (node (ref "E16") (pin "2") (pinfunction "D_2") (pintype "input"))
      (node (ref "E16") (pin "6") (pinfunction "~{Q}_6") (pintype "output"))
      (node (ref "E28") (pin "10") (pinfunction "1A4_10") (pintype "input"))
    )
    (net (code "163") (name "~{BUSEN}") (class "Default")
      (node (ref "E34") (pin "13") (pinfunction "2Y2_13") (pintype "tri_state"))
      (node (ref "J1") (pin "24") (pinfunction "24_24") (pintype "passive"))
    )
    (net (code "164") (name "~{DEP}") (class "Default")
      (node (ref "E28") (pin "5") (pinfunction "1Y2_5") (pintype "tri_state"))
      (node (ref "J2") (pin "20") (pinfunction "20_20") (pintype "passive"))
    )
    (net (code "165") (name "~{DSPLTH}") (class "Default")
      (node (ref "E13") (pin "9") (pinfunction "CLK_9") (pintype "input"))
      (node (ref "E15") (pin "9") (pinfunction "CLK_9") (pintype "input"))
      (node (ref "E8") (pin "8") (pinfunction "O_8") (pintype "output"))
    )
    (net (code "166") (name "~{EMA0}") (class "Default")
      (node (ref "E27") (pin "11") (pinfunction "I_11") (pintype "input"))
      (node (ref "J1") (pin "30") (pinfunction "30_30") (pintype "passive"))
      (node (ref "R34") (pin "2") (pinfunction "2_2") (pintype "passive"))
    )
    (net (code "167") (name "~{EMA1}") (class "Default")
      (node (ref "E27") (pin "9") (pinfunction "I_9") (pintype "input"))
      (node (ref "J1") (pin "28") (pinfunction "28_28") (pintype "passive"))
      (node (ref "R35") (pin "2") (pinfunction "2_2") (pintype "passive"))
    )
    (net (code "168") (name "~{EMA2}") (class "Default")
      (node (ref "E27") (pin "13") (pinfunction "I_13") (pintype "input"))
      (node (ref "J1") (pin "32") (pinfunction "32_32") (pintype "passive"))
      (node (ref "R36") (pin "2") (pinfunction "2_2") (pintype "passive"))
    )
    (net (code "169") (name "~{EMODE}") (class "Default")
      (node (ref "E1") (pin "6") (pinfunction "MOD_6") (pintype "input"))
      (node (ref "E16") (pin "8") (pinfunction "~{Q}_8") (pintype "output"))
      (node (ref "E2") (pin "6") (pinfunction "MOD_6") (pintype "input"))
      (node (ref "E22") (pin "6") (pinfunction "I1_6") (pintype "input"))
      (node (ref "E3") (pin "6") (pinfunction "MOD_6") (pintype "input"))
    )
    (net (code "170") (name "~{EXTPUL}") (class "Default")
      (node (ref "J4") (pin "9") (pinfunction "9_9") (pintype "passive"))
    )
    (net (code "171") (name "~{FUN}") (class "Default")
      (node (ref "E24") (pin "3") (pinfunction "I_3") (pintype "input"))
      (node (ref "E25") (pin "11") (pinfunction "I2_11") (pintype "input"))
      (node (ref "E25") (pin "2") (pinfunction "I1_2") (pintype "input"))
      (node (ref "J4") (pin "15") (pinfunction "15_15") (pintype "passive"))
    )
    (net (code "172") (name "~{GATEENT}") (class "Default")
      (node (ref "E10") (pin "1") (pinfunction "G_1") (pintype "input"))
      (node (ref "E11") (pin "1") (pinfunction "G_1") (pintype "input"))
      (node (ref "E21") (pin "6") (pinfunction "O_6") (pintype "output"))
      (node (ref "E30") (pin "5") (pinfunction "I1_5") (pintype "input"))
      (node (ref "E9") (pin "1") (pinfunction "G_1") (pintype "input"))
    )
    (net (code "173") (name "~{GATESR}") (class "Default")
      (node (ref "E10") (pin "19") (pinfunction "G_19") (pintype "input"))
      (node (ref "E11") (pin "19") (pinfunction "G_19") (pintype "input"))
      (node (ref "E32") (pin "11") (pinfunction "O_11") (pintype "output"))
      (node (ref "E9") (pin "19") (pinfunction "G_19") (pintype "input"))
    )
    (net (code "174") (name "~{IND1}") (class "Default")
      (node (ref "E28") (pin "7") (pinfunction "1Y3_7") (pintype "tri_state"))
      (node (ref "E34") (pin "3") (pinfunction "1Y1_3") (pintype "tri_state"))
      (node (ref "J2") (pin "8") (pinfunction "8_8") (pintype "passive"))
    )
    (net (code "175") (name "~{IND2}") (class "Default")
      (node (ref "E34") (pin "5") (pinfunction "1Y2_5") (pintype "tri_state"))
      (node (ref "J2") (pin "4") (pinfunction "4_4") (pintype "passive"))
    )
    (net (code "176") (name "~{INIT}") (class "Default")
      (node (ref "E31") (pin "9") (pinfunction "1Y4_9") (pintype "tri_state"))
      (node (ref "J2") (pin "34") (pinfunction "34_34") (pintype "passive"))
    )
    (net (code "177") (name "~{KEY-F}") (class "Default")
      (node (ref "E26") (pin "13") (pinfunction "C12_13") (pintype "input"))
      (node (ref "E26") (pin "4") (pinfunction "C34_4") (pintype "input"))
      (node (ref "E27") (pin "5") (pinfunction "I_5") (pintype "input"))
      (node (ref "J4") (pin "3") (pinfunction "3_3") (pintype "passive"))
    )
    (net (code "178") (name "~{KEYCNTL}") (class "Default")
      (node (ref "E31") (pin "13") (pinfunction "2Y2_13") (pintype "tri_state"))
      (node (ref "J2") (pin "10") (pinfunction "10_10") (pintype "passive"))
    )
    (net (code "179") (name "~{KEYSTB}") (class "Default")
      (node (ref "E16") (pin "11") (pinfunction "CLK_11") (pintype "input"))
      (node (ref "E21") (pin "2") (pinfunction "I1_2") (pintype "input"))
      (node (ref "E24") (pin "2") (pinfunction "O_2") (pintype "output"))
      (node (ref "E31") (pin "1") (pinfunction "1G_1") (pintype "input"))
      (node (ref "E33") (pin "11") (pinfunction "I0_11") (pintype "input"))
      (node (ref "E33") (pin "9") (pinfunction "I1_9") (pintype "input"))
    )
    (net (code "180") (name "~{KFUN0}") (class "Default")
      (node (ref "E26") (pin "2") (pinfunction "D1_2") (pintype "input"))
      (node (ref "E3") (pin "1") (pinfunction "SER_1") (pintype "input"))
      (node (ref "E3") (pin "2") (pinfunction "A_2") (pintype "input"))
      (node (ref "J3") (pin "3") (pinfunction "3_3") (pintype "passive"))
    )
    (net (code "181") (name "~{KFUN1}") (class "Default")
      (node (ref "E2") (pin "1") (pinfunction "SER_1") (pintype "input"))
      (node (ref "E2") (pin "2") (pinfunction "A_2") (pintype "input"))
      (node (ref "E26") (pin "3") (pinfunction "D2_3") (pintype "input"))
      (node (ref "J3") (pin "2") (pinfunction "2_2") (pintype "passive"))
    )
    (net (code "182") (name "~{KFUN2}") (class "Default")
      (node (ref "E1") (pin "1") (pinfunction "SER_1") (pintype "input"))
      (node (ref "E1") (pin "2") (pinfunction "A_2") (pintype "input"))
      (node (ref "E26") (pin "6") (pinfunction "D3_6") (pintype "input"))
      (node (ref "J3") (pin "1") (pinfunction "1_1") (pintype "passive"))
    )
    (net (code "183") (name "~{LAENAB}") (class "Default")
      (node (ref "E23") (pin "2") (pinfunction "O_2") (pintype "open_collector"))
      (node (ref "J2") (pin "22") (pinfunction "22_22") (pintype "passive"))
    )
    (net (code "184") (name "~{MAEN}") (class "Default")
      (node (ref "E23") (pin "8") (pinfunction "O_8") (pintype "open_collector"))
      (node (ref "J2") (pin "32") (pinfunction "32_32") (pintype "passive"))
    )
    (net (code "185") (name "~{MALC}") (class "Default")
      (node (ref "E28") (pin "11") (pinfunction "2Y1_11") (pintype "tri_state"))
      (node (ref "J2") (pin "36") (pinfunction "36_36") (pintype "passive"))
    )
    (net (code "186") (name "~{MCLOCK}") (class "Default")
      (node (ref "E33") (pin "2") (pinfunction "I0_2") (pintype "input"))
      (node (ref "J4") (pin "1") (pinfunction "1_1") (pintype "passive"))
    )
    (net (code "187") (name "~{MD}") (class "Default")
      (node (ref "E34") (pin "7") (pinfunction "1Y3_7") (pintype "tri_state"))
      (node (ref "J2") (pin "18") (pinfunction "18_18") (pintype "passive"))
    )
    (net (code "188") (name "~{MEMSTART}") (class "Default")
      (node (ref "E31") (pin "3") (pinfunction "1Y1_3") (pintype "tri_state"))
      (node (ref "E31") (pin "5") (pinfunction "1Y2_5") (pintype "tri_state"))
      (node (ref "J2") (pin "26") (pinfunction "26_26") (pintype "passive"))
    )
    (net (code "189") (name "~{MH0}") (class "Default")
      (node (ref "E20") (pin "12") (pinfunction "D_12") (pintype "input"))
      (node (ref "E20") (pin "8") (pinfunction "~{Q}_8") (pintype "output"))
      (node (ref "E21") (pin "9") (pinfunction "I0_9") (pintype "input"))
      (node (ref "E8") (pin "2") (pinfunction "I1_2") (pintype "input"))
      (node (ref "E8") (pin "9") (pinfunction "I0_9") (pintype "input"))
    )
    (net (code "190") (name "~{MSIRDIS}") (class "Default")
      (node (ref "E31") (pin "11") (pinfunction "2Y1_11") (pintype "tri_state"))
      (node (ref "J2") (pin "2") (pinfunction "2_2") (pintype "passive"))
    )
    (net (code "191") (name "~{PANLOCK}") (class "Default")
      (node (ref "E24") (pin "13") (pinfunction "I_13") (pintype "input"))
      (node (ref "J2") (pin "6") (pinfunction "6_6") (pintype "passive"))
      (node (ref "R31") (pin "1") (pinfunction "1_1") (pintype "passive"))
    )
    (net (code "192") (name "~{PULSELOADADD}") (class "Default")
      (node (ref "E31") (pin "7") (pinfunction "1Y3_7") (pintype "tri_state"))
      (node (ref "J2") (pin "40") (pinfunction "40_40") (pintype "passive"))
    )
    (net (code "193") (name "~{RUN}") (class "Default")
      (node (ref "E24") (pin "5") (pinfunction "I_5") (pintype "input"))
      (node (ref "J1") (pin "18") (pinfunction "18_18") (pintype "passive"))
      (node (ref "R28") (pin "1") (pinfunction "1_1") (pintype "passive"))
    )
    (net (code "194") (name "~{SHLT}") (class "Default")
      (node (ref "E27") (pin "1") (pinfunction "I_1") (pintype "input"))
      (node (ref "J3") (pin "5") (pinfunction "5_5") (pintype "passive"))
    )
    (net (code "195") (name "~{SINGSTEP}") (class "Default")
      (node (ref "E28") (pin "13") (pinfunction "2Y2_13") (pintype "tri_state"))
      (node (ref "J2") (pin "14") (pinfunction "14_14") (pintype "passive"))
    )
    (net (code "196") (name "~{SRDATA}") (class "Default")
      (node (ref "E32") (pin "13") (pinfunction "I1_13") (pintype "input"))
      (node (ref "E8") (pin "1") (pinfunction "I0_1") (pintype "input"))
      (node (ref "J2") (pin "30") (pinfunction "30_30") (pintype "passive"))
      (node (ref "R29") (pin "1") (pinfunction "1_1") (pintype "passive"))
      (node (ref "R30") (pin "2") (pinfunction "2_2") (pintype "passive"))
    )
    (net (code "197") (name "~{STATE}") (class "Default")
      (node (ref "E34") (pin "11") (pinfunction "2Y1_11") (pintype "tri_state"))
      (node (ref "J2") (pin "38") (pinfunction "38_38") (pintype "passive"))
    )
    (net (code "198") (name "~{STHIS}") (class "Default")
      (node (ref "E20") (pin "2") (pinfunction "D_2") (pintype "input"))
      (node (ref "J3") (pin "4") (pinfunction "4_4") (pintype "passive"))
    )
    (net (code "199") (name "~{TSI}") (class "Default")
      (node (ref "E20") (pin "3") (pinfunction "CLK_3") (pintype "input"))
      (node (ref "E21") (pin "10") (pinfunction "I1_10") (pintype "input"))
      (node (ref "E24") (pin "9") (pinfunction "I_9") (pintype "input"))
      (node (ref "J1") (pin "26") (pinfunction "26_26") (pintype "passive"))
      (node (ref "R26") (pin "1") (pinfunction "1_1") (pintype "passive"))
      (node (ref "R27") (pin "2") (pinfunction "2_2") (pintype "passive"))
    )
  )
)
